# untitled.net
KiCad netlist of a schematic drawn in EAGLE
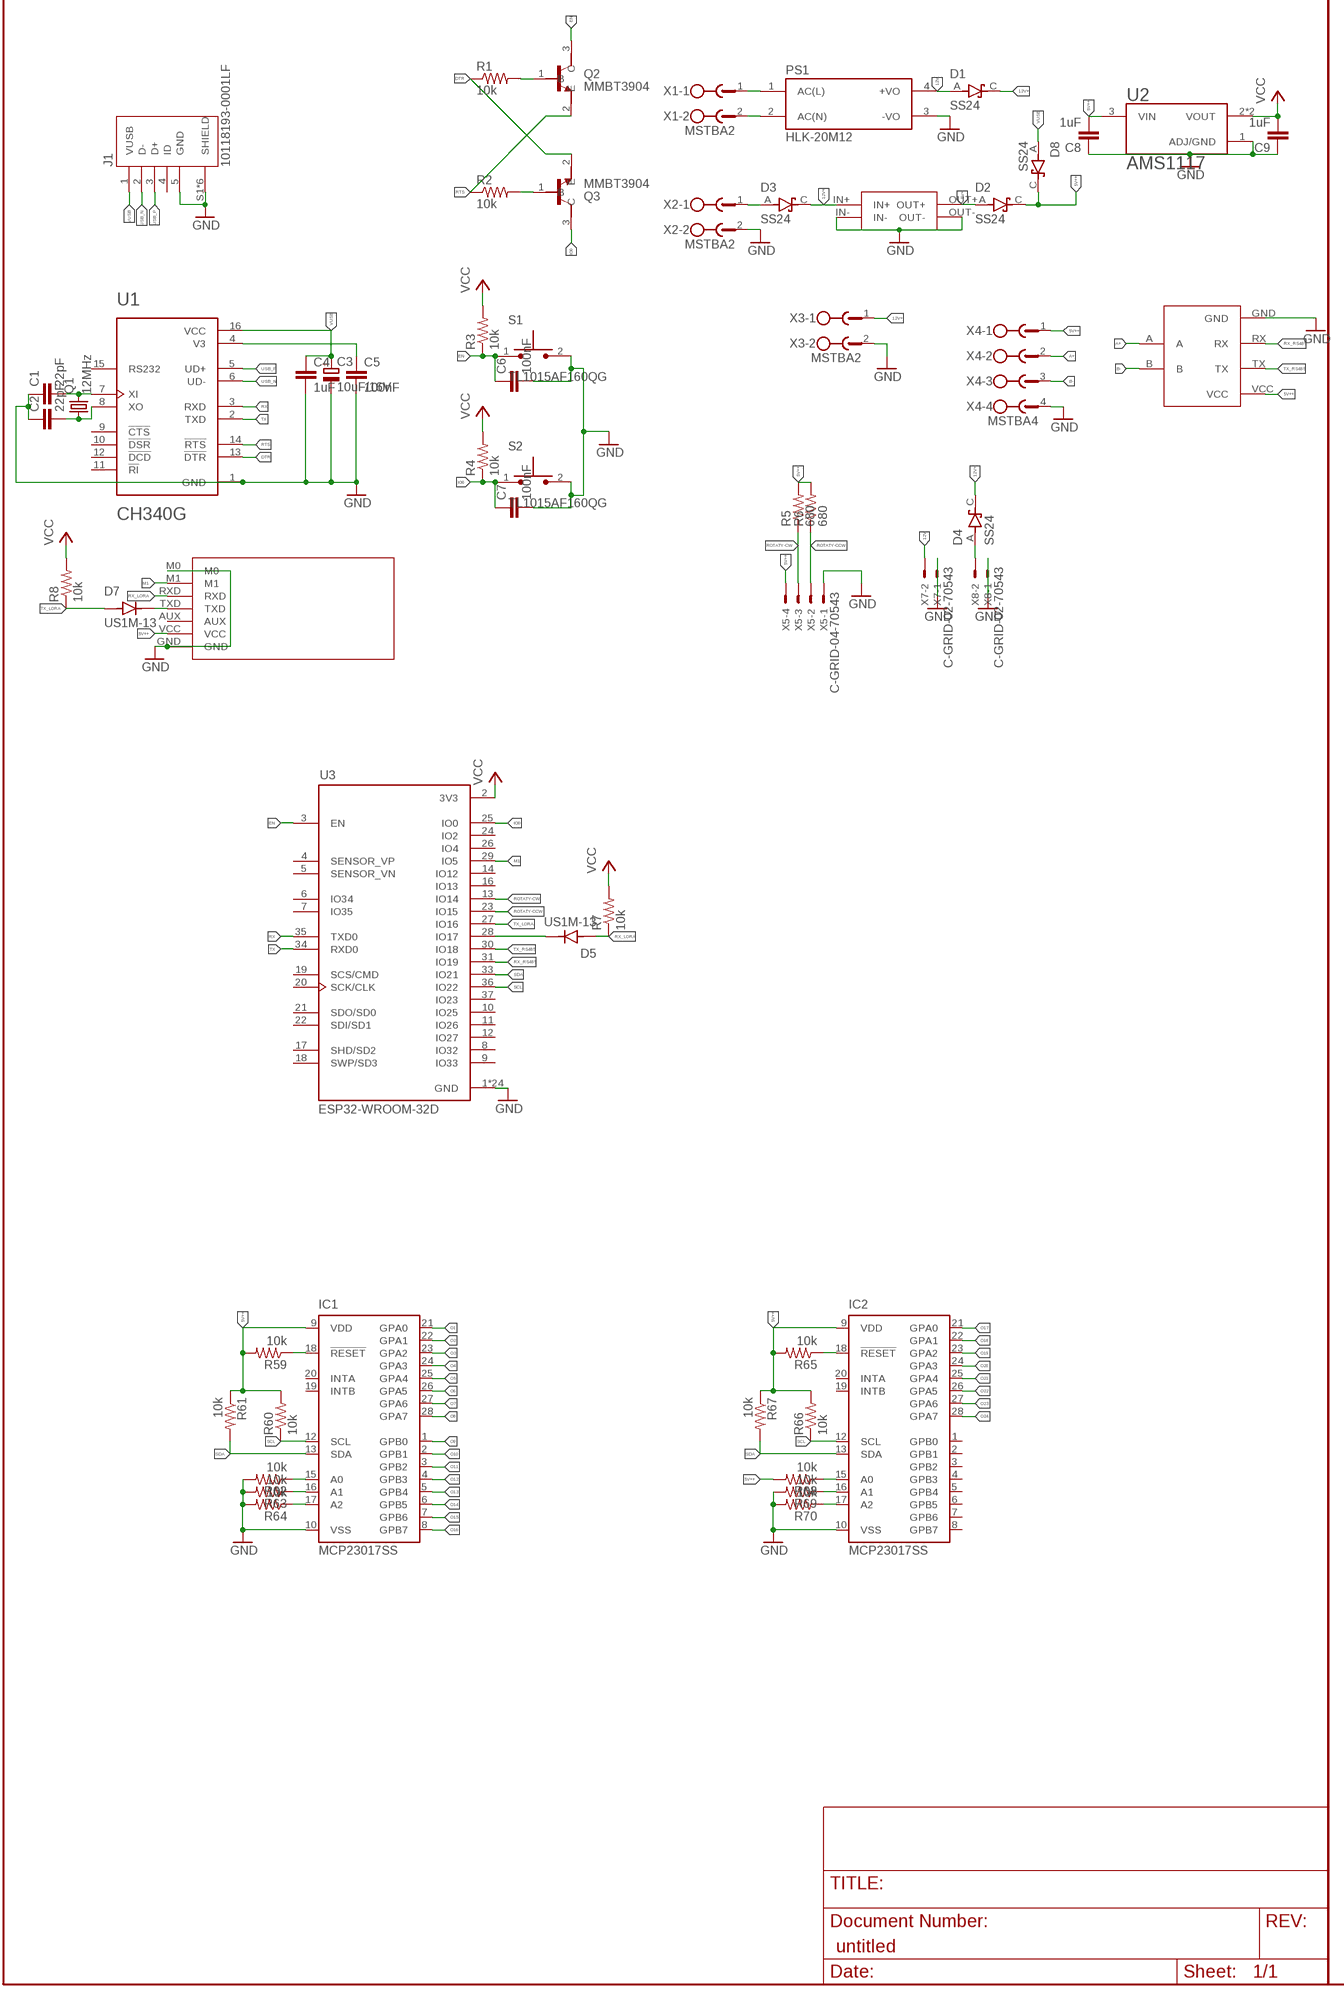
[diagram p0: schematic, sheet 1, part 1 of 2]
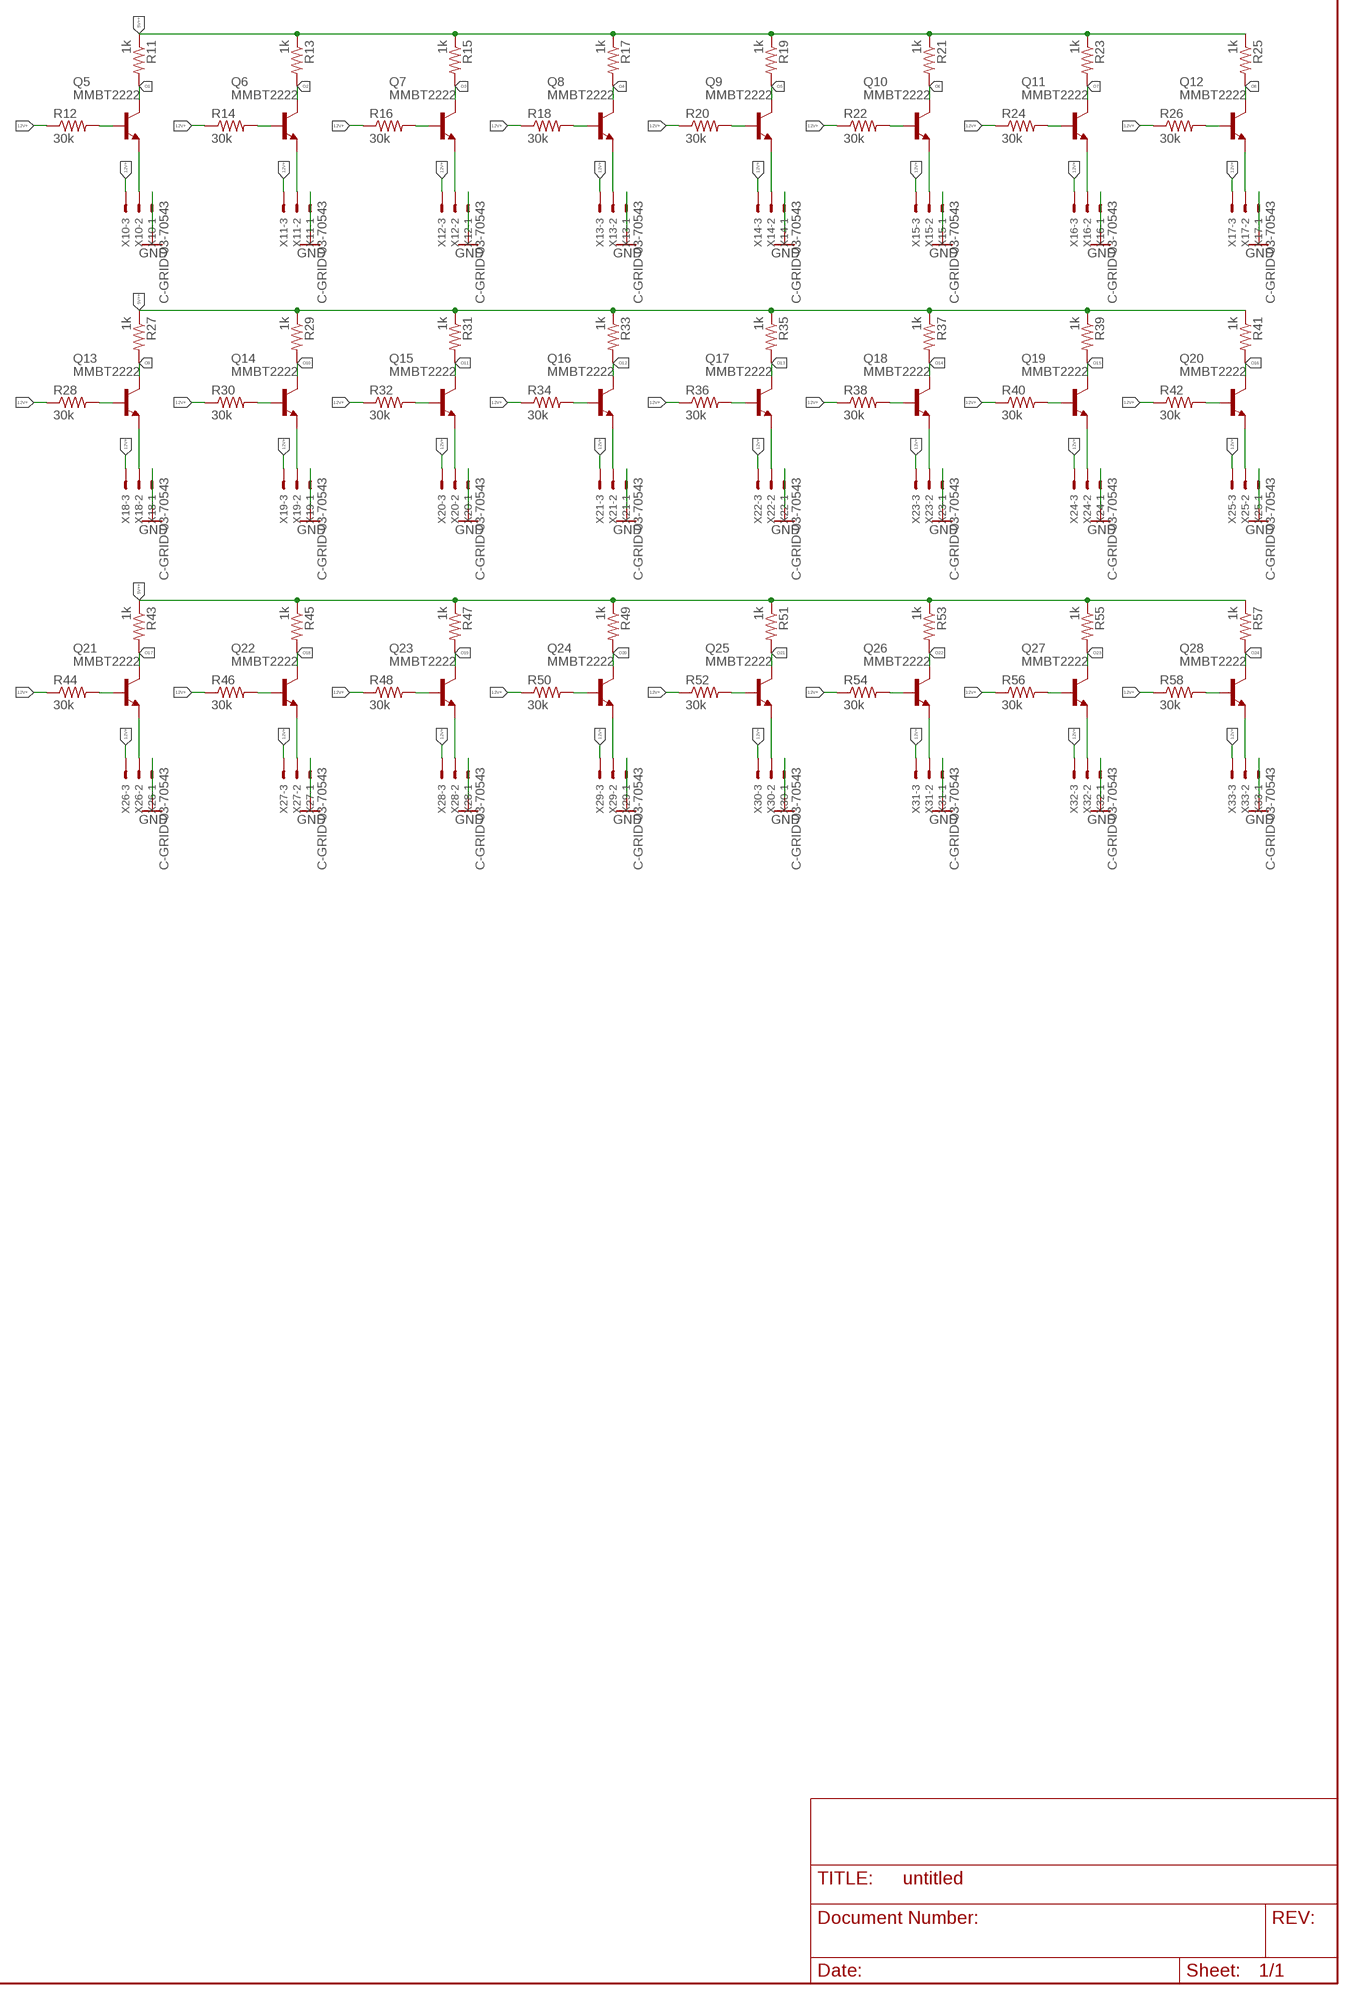
[diagram p1: schematic, sheet 1, part 2 of 2]

(export (version "E")
  (design (tool "Eeschema 10.0.6"))
  (components
    (comp (ref "C1")
      (value "22pF")
      (footprint "eagle-import:C0805K")
      (libsource (lib "eagle-import") (part "C-EUC0805K"))
    )
    (comp (ref "C2")
      (value "22pF")
      (footprint "eagle-import:C0805K")
      (libsource (lib "eagle-import") (part "C-EUC0805K"))
    )
    (comp (ref "C3")
      (value "10uF/16V")
      (footprint "eagle-import:153CLV-0505")
      (libsource (lib "eagle-import") (part "CPOL-EU153CLV-0505"))
    )
    (comp (ref "C4")
      (value "1uF")
      (footprint "eagle-import:C0805K")
      (libsource (lib "eagle-import") (part "C-EUC0805K"))
    )
    (comp (ref "C5")
      (value "100nF")
      (footprint "eagle-import:C0805K")
      (libsource (lib "eagle-import") (part "C-EUC0805K"))
    )
    (comp (ref "C6")
      (value "100nF")
      (footprint "eagle-import:C0805K")
      (libsource (lib "eagle-import") (part "C-EUC0805K"))
    )
    (comp (ref "C7")
      (value "100nF")
      (footprint "eagle-import:C0805K")
      (libsource (lib "eagle-import") (part "C-EUC0805K"))
    )
    (comp (ref "C8")
      (value "1uF")
      (footprint "eagle-import:C0805K")
      (libsource (lib "eagle-import") (part "C-EUC0805K"))
    )
    (comp (ref "C9")
      (value "1uF")
      (footprint "eagle-import:C0805K")
      (libsource (lib "eagle-import") (part "C-EUC0805K"))
    )
    (comp (ref "D1")
      (value "SS24")
      (footprint "eagle-import:DIOM5336X265N")
      (fields (field (name "MF") "ON Semiconductor"))
      (libsource (lib "eagle-import") (part "SS24"))
    )
    (comp (ref "D2")
      (value "SS24")
      (footprint "eagle-import:DIOM5336X265N")
      (fields (field (name "MF") "ON Semiconductor"))
      (libsource (lib "eagle-import") (part "SS24"))
    )
    (comp (ref "D3")
      (value "SS24")
      (footprint "eagle-import:DIOM5336X265N")
      (fields (field (name "MF") "ON Semiconductor"))
      (libsource (lib "eagle-import") (part "SS24"))
    )
    (comp (ref "D4")
      (value "SS24")
      (footprint "eagle-import:DIOM5336X265N")
      (fields (field (name "MF") "ON Semiconductor"))
      (libsource (lib "eagle-import") (part "SS24"))
    )
    (comp (ref "D5")
      (value "US1M-13")
      (footprint "eagle-import:DIOM5226X240N")
      (fields (field (name "MF") "Diodes Incorporated"))
      (libsource (lib "eagle-import") (part "US1M-13"))
    )
    (comp (ref "D7")
      (value "US1M-13")
      (footprint "eagle-import:DIOM5226X240N")
      (fields (field (name "MF") "Diodes Incorporated"))
      (libsource (lib "eagle-import") (part "US1M-13"))
    )
    (comp (ref "D8")
      (value "SS24")
      (footprint "eagle-import:DIOM5336X265N")
      (fields (field (name "MF") "ON Semiconductor"))
      (libsource (lib "eagle-import") (part "SS24"))
    )
    (comp (ref "EBYTEE220-900T22D1")
      (value "EBYTEE220-900T22D")
      (footprint "eagle-import:EBYTEE220-900T22D")
      (libsource (lib "eagle-import") (part "EBYTEE220-900T22D"))
    )
    (comp (ref "IC1")
      (value "MCP23017SS")
      (footprint "eagle-import:SSOP28")
      (libsource (lib "eagle-import") (part "MCP23017SS"))
    )
    (comp (ref "IC2")
      (value "MCP23017SS")
      (footprint "eagle-import:SSOP28")
      (libsource (lib "eagle-import") (part "MCP23017SS"))
    )
    (comp (ref "J1")
      (value "10118193-0001LF")
      (footprint "eagle-import:FCI_10118193-0001LF")
      (fields (field (name "MF") "FCI"))
      (libsource (lib "eagle-import") (part "10118193-0001LF"))
    )
    (comp (ref "MINI1")
      (value "MINI560")
      (footprint "eagle-import:MINI560")
      (libsource (lib "eagle-import") (part "MINI560"))
    )
    (comp (ref "PS1")
      (value "HLK-20M12")
      (footprint "eagle-import:CONV_HLK-20M12")
      (fields (field (name "MF") "Hi-link"))
      (libsource (lib "eagle-import") (part "HLK-20M12"))
    )
    (comp (ref "Q1")
      (value "12MHz")
      (footprint "eagle-import:SM49")
      (libsource (lib "eagle-import") (part "CRYSTALSM49"))
    )
    (comp (ref "Q2")
      (value "MMBT3904")
      (footprint "eagle-import:SOT95P240X120-3N")
      (fields (field (name "MF") "ON Semiconductor"))
      (libsource (lib "eagle-import") (part "MMBT3904"))
    )
    (comp (ref "Q3")
      (value "MMBT3904")
      (footprint "eagle-import:SOT95P240X120-3N")
      (fields (field (name "MF") "ON Semiconductor"))
      (libsource (lib "eagle-import") (part "MMBT3904"))
    )
    (comp (ref "Q5")
      (value "MMBT2222")
      (footprint "eagle-import:SOT23-BEC")
      (fields (field (name "MF") "ON Semiconductor"))
      (libsource (lib "eagle-import") (part "MMBT2222"))
    )
    (comp (ref "Q6")
      (value "MMBT2222")
      (footprint "eagle-import:SOT23-BEC")
      (fields (field (name "MF") "ON Semiconductor"))
      (libsource (lib "eagle-import") (part "MMBT2222"))
    )
    (comp (ref "Q7")
      (value "MMBT2222")
      (footprint "eagle-import:SOT23-BEC")
      (fields (field (name "MF") "ON Semiconductor"))
      (libsource (lib "eagle-import") (part "MMBT2222"))
    )
    (comp (ref "Q8")
      (value "MMBT2222")
      (footprint "eagle-import:SOT23-BEC")
      (fields (field (name "MF") "ON Semiconductor"))
      (libsource (lib "eagle-import") (part "MMBT2222"))
    )
    (comp (ref "Q9")
      (value "MMBT2222")
      (footprint "eagle-import:SOT23-BEC")
      (fields (field (name "MF") "ON Semiconductor"))
      (libsource (lib "eagle-import") (part "MMBT2222"))
    )
    (comp (ref "Q10")
      (value "MMBT2222")
      (footprint "eagle-import:SOT23-BEC")
      (fields (field (name "MF") "ON Semiconductor"))
      (libsource (lib "eagle-import") (part "MMBT2222"))
    )
    (comp (ref "Q11")
      (value "MMBT2222")
      (footprint "eagle-import:SOT23-BEC")
      (fields (field (name "MF") "ON Semiconductor"))
      (libsource (lib "eagle-import") (part "MMBT2222"))
    )
    (comp (ref "Q12")
      (value "MMBT2222")
      (footprint "eagle-import:SOT23-BEC")
      (fields (field (name "MF") "ON Semiconductor"))
      (libsource (lib "eagle-import") (part "MMBT2222"))
    )
    (comp (ref "Q13")
      (value "MMBT2222")
      (footprint "eagle-import:SOT23-BEC")
      (fields (field (name "MF") "ON Semiconductor"))
      (libsource (lib "eagle-import") (part "MMBT2222"))
    )
    (comp (ref "Q14")
      (value "MMBT2222")
      (footprint "eagle-import:SOT23-BEC")
      (fields (field (name "MF") "ON Semiconductor"))
      (libsource (lib "eagle-import") (part "MMBT2222"))
    )
    (comp (ref "Q15")
      (value "MMBT2222")
      (footprint "eagle-import:SOT23-BEC")
      (fields (field (name "MF") "ON Semiconductor"))
      (libsource (lib "eagle-import") (part "MMBT2222"))
    )
    (comp (ref "Q16")
      (value "MMBT2222")
      (footprint "eagle-import:SOT23-BEC")
      (fields (field (name "MF") "ON Semiconductor"))
      (libsource (lib "eagle-import") (part "MMBT2222"))
    )
    (comp (ref "Q17")
      (value "MMBT2222")
      (footprint "eagle-import:SOT23-BEC")
      (fields (field (name "MF") "ON Semiconductor"))
      (libsource (lib "eagle-import") (part "MMBT2222"))
    )
    (comp (ref "Q18")
      (value "MMBT2222")
      (footprint "eagle-import:SOT23-BEC")
      (fields (field (name "MF") "ON Semiconductor"))
      (libsource (lib "eagle-import") (part "MMBT2222"))
    )
    (comp (ref "Q19")
      (value "MMBT2222")
      (footprint "eagle-import:SOT23-BEC")
      (fields (field (name "MF") "ON Semiconductor"))
      (libsource (lib "eagle-import") (part "MMBT2222"))
    )
    (comp (ref "Q20")
      (value "MMBT2222")
      (footprint "eagle-import:SOT23-BEC")
      (fields (field (name "MF") "ON Semiconductor"))
      (libsource (lib "eagle-import") (part "MMBT2222"))
    )
    (comp (ref "Q21")
      (value "MMBT2222")
      (footprint "eagle-import:SOT23-BEC")
      (fields (field (name "MF") "ON Semiconductor"))
      (libsource (lib "eagle-import") (part "MMBT2222"))
    )
    (comp (ref "Q22")
      (value "MMBT2222")
      (footprint "eagle-import:SOT23-BEC")
      (fields (field (name "MF") "ON Semiconductor"))
      (libsource (lib "eagle-import") (part "MMBT2222"))
    )
    (comp (ref "Q23")
      (value "MMBT2222")
      (footprint "eagle-import:SOT23-BEC")
      (fields (field (name "MF") "ON Semiconductor"))
      (libsource (lib "eagle-import") (part "MMBT2222"))
    )
    (comp (ref "Q24")
      (value "MMBT2222")
      (footprint "eagle-import:SOT23-BEC")
      (fields (field (name "MF") "ON Semiconductor"))
      (libsource (lib "eagle-import") (part "MMBT2222"))
    )
    (comp (ref "Q25")
      (value "MMBT2222")
      (footprint "eagle-import:SOT23-BEC")
      (fields (field (name "MF") "ON Semiconductor"))
      (libsource (lib "eagle-import") (part "MMBT2222"))
    )
    (comp (ref "Q26")
      (value "MMBT2222")
      (footprint "eagle-import:SOT23-BEC")
      (fields (field (name "MF") "ON Semiconductor"))
      (libsource (lib "eagle-import") (part "MMBT2222"))
    )
    (comp (ref "Q27")
      (value "MMBT2222")
      (footprint "eagle-import:SOT23-BEC")
      (fields (field (name "MF") "ON Semiconductor"))
      (libsource (lib "eagle-import") (part "MMBT2222"))
    )
    (comp (ref "Q28")
      (value "MMBT2222")
      (footprint "eagle-import:SOT23-BEC")
      (fields (field (name "MF") "ON Semiconductor"))
      (libsource (lib "eagle-import") (part "MMBT2222"))
    )
    (comp (ref "R1")
      (value "10k")
      (footprint "eagle-import:M0805")
      (libsource (lib "eagle-import") (part "R-US_M0805"))
    )
    (comp (ref "R2")
      (value "10k")
      (footprint "eagle-import:M0805")
      (libsource (lib "eagle-import") (part "R-US_M0805"))
    )
    (comp (ref "R3")
      (value "10k")
      (footprint "eagle-import:M0805")
      (libsource (lib "eagle-import") (part "R-US_M0805"))
    )
    (comp (ref "R4")
      (value "10k")
      (footprint "eagle-import:M0805")
      (libsource (lib "eagle-import") (part "R-US_M0805"))
    )
    (comp (ref "R5")
      (value "680")
      (footprint "eagle-import:M0805")
      (libsource (lib "eagle-import") (part "R-US_M0805"))
    )
    (comp (ref "R6")
      (value "680")
      (footprint "eagle-import:M0805")
      (libsource (lib "eagle-import") (part "R-US_M0805"))
    )
    (comp (ref "R7")
      (value "10k")
      (footprint "eagle-import:M0805")
      (libsource (lib "eagle-import") (part "R-US_M0805"))
    )
    (comp (ref "R8")
      (value "10k")
      (footprint "eagle-import:M0805")
      (libsource (lib "eagle-import") (part "R-US_M0805"))
    )
    (comp (ref "R11")
      (value "1k")
      (footprint "eagle-import:M0805")
      (libsource (lib "eagle-import") (part "R-US_M0805"))
    )
    (comp (ref "R12")
      (value "30k")
      (footprint "eagle-import:M0805")
      (libsource (lib "eagle-import") (part "R-US_M0805"))
    )
    (comp (ref "R13")
      (value "1k")
      (footprint "eagle-import:M0805")
      (libsource (lib "eagle-import") (part "R-US_M0805"))
    )
    (comp (ref "R14")
      (value "30k")
      (footprint "eagle-import:M0805")
      (libsource (lib "eagle-import") (part "R-US_M0805"))
    )
    (comp (ref "R15")
      (value "1k")
      (footprint "eagle-import:M0805")
      (libsource (lib "eagle-import") (part "R-US_M0805"))
    )
    (comp (ref "R16")
      (value "30k")
      (footprint "eagle-import:M0805")
      (libsource (lib "eagle-import") (part "R-US_M0805"))
    )
    (comp (ref "R17")
      (value "1k")
      (footprint "eagle-import:M0805")
      (libsource (lib "eagle-import") (part "R-US_M0805"))
    )
    (comp (ref "R18")
      (value "30k")
      (footprint "eagle-import:M0805")
      (libsource (lib "eagle-import") (part "R-US_M0805"))
    )
    (comp (ref "R19")
      (value "1k")
      (footprint "eagle-import:M0805")
      (libsource (lib "eagle-import") (part "R-US_M0805"))
    )
    (comp (ref "R20")
      (value "30k")
      (footprint "eagle-import:M0805")
      (libsource (lib "eagle-import") (part "R-US_M0805"))
    )
    (comp (ref "R21")
      (value "1k")
      (footprint "eagle-import:M0805")
      (libsource (lib "eagle-import") (part "R-US_M0805"))
    )
    (comp (ref "R22")
      (value "30k")
      (footprint "eagle-import:M0805")
      (libsource (lib "eagle-import") (part "R-US_M0805"))
    )
    (comp (ref "R23")
      (value "1k")
      (footprint "eagle-import:M0805")
      (libsource (lib "eagle-import") (part "R-US_M0805"))
    )
    (comp (ref "R24")
      (value "30k")
      (footprint "eagle-import:M0805")
      (libsource (lib "eagle-import") (part "R-US_M0805"))
    )
    (comp (ref "R25")
      (value "1k")
      (footprint "eagle-import:M0805")
      (libsource (lib "eagle-import") (part "R-US_M0805"))
    )
    (comp (ref "R26")
      (value "30k")
      (footprint "eagle-import:M0805")
      (libsource (lib "eagle-import") (part "R-US_M0805"))
    )
    (comp (ref "R27")
      (value "1k")
      (footprint "eagle-import:M0805")
      (libsource (lib "eagle-import") (part "R-US_M0805"))
    )
    (comp (ref "R28")
      (value "30k")
      (footprint "eagle-import:M0805")
      (libsource (lib "eagle-import") (part "R-US_M0805"))
    )
    (comp (ref "R29")
      (value "1k")
      (footprint "eagle-import:M0805")
      (libsource (lib "eagle-import") (part "R-US_M0805"))
    )
    (comp (ref "R30")
      (value "30k")
      (footprint "eagle-import:M0805")
      (libsource (lib "eagle-import") (part "R-US_M0805"))
    )
    (comp (ref "R31")
      (value "1k")
      (footprint "eagle-import:M0805")
      (libsource (lib "eagle-import") (part "R-US_M0805"))
    )
    (comp (ref "R32")
      (value "30k")
      (footprint "eagle-import:M0805")
      (libsource (lib "eagle-import") (part "R-US_M0805"))
    )
    (comp (ref "R33")
      (value "1k")
      (footprint "eagle-import:M0805")
      (libsource (lib "eagle-import") (part "R-US_M0805"))
    )
    (comp (ref "R34")
      (value "30k")
      (footprint "eagle-import:M0805")
      (libsource (lib "eagle-import") (part "R-US_M0805"))
    )
    (comp (ref "R35")
      (value "1k")
      (footprint "eagle-import:M0805")
      (libsource (lib "eagle-import") (part "R-US_M0805"))
    )
    (comp (ref "R36")
      (value "30k")
      (footprint "eagle-import:M0805")
      (libsource (lib "eagle-import") (part "R-US_M0805"))
    )
    (comp (ref "R37")
      (value "1k")
      (footprint "eagle-import:M0805")
      (libsource (lib "eagle-import") (part "R-US_M0805"))
    )
    (comp (ref "R38")
      (value "30k")
      (footprint "eagle-import:M0805")
      (libsource (lib "eagle-import") (part "R-US_M0805"))
    )
    (comp (ref "R39")
      (value "1k")
      (footprint "eagle-import:M0805")
      (libsource (lib "eagle-import") (part "R-US_M0805"))
    )
    (comp (ref "R40")
      (value "30k")
      (footprint "eagle-import:M0805")
      (libsource (lib "eagle-import") (part "R-US_M0805"))
    )
    (comp (ref "R41")
      (value "1k")
      (footprint "eagle-import:M0805")
      (libsource (lib "eagle-import") (part "R-US_M0805"))
    )
    (comp (ref "R42")
      (value "30k")
      (footprint "eagle-import:M0805")
      (libsource (lib "eagle-import") (part "R-US_M0805"))
    )
    (comp (ref "R43")
      (value "1k")
      (footprint "eagle-import:M0805")
      (libsource (lib "eagle-import") (part "R-US_M0805"))
    )
    (comp (ref "R44")
      (value "30k")
      (footprint "eagle-import:M0805")
      (libsource (lib "eagle-import") (part "R-US_M0805"))
    )
    (comp (ref "R45")
      (value "1k")
      (footprint "eagle-import:M0805")
      (libsource (lib "eagle-import") (part "R-US_M0805"))
    )
    (comp (ref "R46")
      (value "30k")
      (footprint "eagle-import:M0805")
      (libsource (lib "eagle-import") (part "R-US_M0805"))
    )
    (comp (ref "R47")
      (value "1k")
      (footprint "eagle-import:M0805")
      (libsource (lib "eagle-import") (part "R-US_M0805"))
    )
    (comp (ref "R48")
      (value "30k")
      (footprint "eagle-import:M0805")
      (libsource (lib "eagle-import") (part "R-US_M0805"))
    )
    (comp (ref "R49")
      (value "1k")
      (footprint "eagle-import:M0805")
      (libsource (lib "eagle-import") (part "R-US_M0805"))
    )
    (comp (ref "R50")
      (value "30k")
      (footprint "eagle-import:M0805")
      (libsource (lib "eagle-import") (part "R-US_M0805"))
    )
    (comp (ref "R51")
      (value "1k")
      (footprint "eagle-import:M0805")
      (libsource (lib "eagle-import") (part "R-US_M0805"))
    )
    (comp (ref "R52")
      (value "30k")
      (footprint "eagle-import:M0805")
      (libsource (lib "eagle-import") (part "R-US_M0805"))
    )
    (comp (ref "R53")
      (value "1k")
      (footprint "eagle-import:M0805")
      (libsource (lib "eagle-import") (part "R-US_M0805"))
    )
    (comp (ref "R54")
      (value "30k")
      (footprint "eagle-import:M0805")
      (libsource (lib "eagle-import") (part "R-US_M0805"))
    )
    (comp (ref "R55")
      (value "1k")
      (footprint "eagle-import:M0805")
      (libsource (lib "eagle-import") (part "R-US_M0805"))
    )
    (comp (ref "R56")
      (value "30k")
      (footprint "eagle-import:M0805")
      (libsource (lib "eagle-import") (part "R-US_M0805"))
    )
    (comp (ref "R57")
      (value "1k")
      (footprint "eagle-import:M0805")
      (libsource (lib "eagle-import") (part "R-US_M0805"))
    )
    (comp (ref "R58")
      (value "30k")
      (footprint "eagle-import:M0805")
      (libsource (lib "eagle-import") (part "R-US_M0805"))
    )
    (comp (ref "R59")
      (value "10k")
      (footprint "eagle-import:M0805")
      (libsource (lib "eagle-import") (part "R-US_M0805"))
    )
    (comp (ref "R60")
      (value "10k")
      (footprint "eagle-import:M0805")
      (libsource (lib "eagle-import") (part "R-US_M0805"))
    )
    (comp (ref "R61")
      (value "10k")
      (footprint "eagle-import:M0805")
      (libsource (lib "eagle-import") (part "R-US_M0805"))
    )
    (comp (ref "R62")
      (value "10k")
      (footprint "eagle-import:M0805")
      (libsource (lib "eagle-import") (part "R-US_M0805"))
    )
    (comp (ref "R63")
      (value "10k")
      (footprint "eagle-import:M0805")
      (libsource (lib "eagle-import") (part "R-US_M0805"))
    )
    (comp (ref "R64")
      (value "10k")
      (footprint "eagle-import:M0805")
      (libsource (lib "eagle-import") (part "R-US_M0805"))
    )
    (comp (ref "R65")
      (value "10k")
      (footprint "eagle-import:M0805")
      (libsource (lib "eagle-import") (part "R-US_M0805"))
    )
    (comp (ref "R66")
      (value "10k")
      (footprint "eagle-import:M0805")
      (libsource (lib "eagle-import") (part "R-US_M0805"))
    )
    (comp (ref "R67")
      (value "10k")
      (footprint "eagle-import:M0805")
      (libsource (lib "eagle-import") (part "R-US_M0805"))
    )
    (comp (ref "R68")
      (value "10k")
      (footprint "eagle-import:M0805")
      (libsource (lib "eagle-import") (part "R-US_M0805"))
    )
    (comp (ref "R69")
      (value "10k")
      (footprint "eagle-import:M0805")
      (libsource (lib "eagle-import") (part "R-US_M0805"))
    )
    (comp (ref "R70")
      (value "10k")
      (footprint "eagle-import:M0805")
      (libsource (lib "eagle-import") (part "R-US_M0805"))
    )
    (comp (ref "S1")
      (value "TL1015AF160QG")
      (footprint "eagle-import:SW_TL1015AF160QG")
      (fields (field (name "MF") "E-Switch"))
      (libsource (lib "eagle-import") (part "TL1015AF160QG"))
    )
    (comp (ref "S2")
      (value "TL1015AF160QG")
      (footprint "eagle-import:SW_TL1015AF160QG")
      (fields (field (name "MF") "E-Switch"))
      (libsource (lib "eagle-import") (part "TL1015AF160QG"))
    )
    (comp (ref "TTL-RS1")
      (value "TTL-RS485")
      (footprint "eagle-import:TTL-RS485")
      (libsource (lib "eagle-import") (part "TTL-RS485"))
    )
    (comp (ref "U1")
      (value "CH340G")
      (footprint "eagle-import:SOIC127P600X180-16N")
      (fields (field (name "MF") "WCH") (field (name "MP") "Ch340G"))
      (libsource (lib "eagle-import") (part "CH340G"))
    )
    (comp (ref "U2")
      (value "AMS1117")
      (footprint "eagle-import:SOT229P700X180-4N")
      (fields (field (name "MF") "Advanced Monolithic Systems"))
      (libsource (lib "eagle-import") (part "AMS1117"))
    )
    (comp (ref "U3")
      (value "ESP32-WROOM-32D")
      (footprint "eagle-import:MODULE_ESP32-WROOM-32D")
      (fields (field (name "MF") "Espressif Systems"))
      (libsource (lib "eagle-import") (part "ESP32-WROOM-32D"))
    )
    (comp (ref "X1")
      (value "MSTBA2")
      (footprint "eagle-import:MSTBA2")
      (fields (field (name "MF") "FARNELL") (field (name "MPN") "1757242"))
      (libsource (lib "eagle-import") (part "MSTBA2"))
    )
    (comp (ref "X2")
      (value "MSTBA2")
      (footprint "eagle-import:MSTBA2")
      (fields (field (name "MF") "FARNELL") (field (name "MPN") "1757242"))
      (libsource (lib "eagle-import") (part "MSTBA2"))
    )
    (comp (ref "X3")
      (value "MSTBA2")
      (footprint "eagle-import:MSTBA2")
      (fields (field (name "MF") "FARNELL") (field (name "MPN") "1757242"))
      (libsource (lib "eagle-import") (part "MSTBA2"))
    )
    (comp (ref "X4")
      (value "MSTBA4")
      (footprint "eagle-import:MSTBA4")
      (fields (field (name "MF") "FARNELL") (field (name "MPN") "1757268"))
      (libsource (lib "eagle-import") (part "MSTBA4"))
    )
    (comp (ref "X5")
      (value "C-GRID-04-70543")
      (footprint "eagle-import:70543-04")
      (fields (field (name "MF") "MOLEX"))
      (libsource (lib "eagle-import") (part "C-GRID-04-70543"))
    )
    (comp (ref "X7")
      (value "C-GRID-02-70543")
      (footprint "eagle-import:70543-02")
      (fields (field (name "MF") "MOLEX"))
      (libsource (lib "eagle-import") (part "C-GRID-02-70543"))
    )
    (comp (ref "X8")
      (value "C-GRID-02-70543")
      (footprint "eagle-import:70543-02")
      (fields (field (name "MF") "MOLEX"))
      (libsource (lib "eagle-import") (part "C-GRID-02-70543"))
    )
    (comp (ref "X10")
      (value "C-GRID-03-70543")
      (footprint "eagle-import:70543-03")
      (fields (field (name "MF") "MOLEX"))
      (libsource (lib "eagle-import") (part "C-GRID-03-70543"))
    )
    (comp (ref "X11")
      (value "C-GRID-03-70543")
      (footprint "eagle-import:70543-03")
      (fields (field (name "MF") "MOLEX"))
      (libsource (lib "eagle-import") (part "C-GRID-03-70543"))
    )
    (comp (ref "X12")
      (value "C-GRID-03-70543")
      (footprint "eagle-import:70543-03")
      (fields (field (name "MF") "MOLEX"))
      (libsource (lib "eagle-import") (part "C-GRID-03-70543"))
    )
    (comp (ref "X13")
      (value "C-GRID-03-70543")
      (footprint "eagle-import:70543-03")
      (fields (field (name "MF") "MOLEX"))
      (libsource (lib "eagle-import") (part "C-GRID-03-70543"))
    )
    (comp (ref "X14")
      (value "C-GRID-03-70543")
      (footprint "eagle-import:70543-03")
      (fields (field (name "MF") "MOLEX"))
      (libsource (lib "eagle-import") (part "C-GRID-03-70543"))
    )
    (comp (ref "X15")
      (value "C-GRID-03-70543")
      (footprint "eagle-import:70543-03")
      (fields (field (name "MF") "MOLEX"))
      (libsource (lib "eagle-import") (part "C-GRID-03-70543"))
    )
    (comp (ref "X16")
      (value "C-GRID-03-70543")
      (footprint "eagle-import:70543-03")
      (fields (field (name "MF") "MOLEX"))
      (libsource (lib "eagle-import") (part "C-GRID-03-70543"))
    )
    (comp (ref "X17")
      (value "C-GRID-03-70543")
      (footprint "eagle-import:70543-03")
      (fields (field (name "MF") "MOLEX"))
      (libsource (lib "eagle-import") (part "C-GRID-03-70543"))
    )
    (comp (ref "X18")
      (value "C-GRID-03-70543")
      (footprint "eagle-import:70543-03")
      (fields (field (name "MF") "MOLEX"))
      (libsource (lib "eagle-import") (part "C-GRID-03-70543"))
    )
    (comp (ref "X19")
      (value "C-GRID-03-70543")
      (footprint "eagle-import:70543-03")
      (fields (field (name "MF") "MOLEX"))
      (libsource (lib "eagle-import") (part "C-GRID-03-70543"))
    )
    (comp (ref "X20")
      (value "C-GRID-03-70543")
      (footprint "eagle-import:70543-03")
      (fields (field (name "MF") "MOLEX"))
      (libsource (lib "eagle-import") (part "C-GRID-03-70543"))
    )
    (comp (ref "X21")
      (value "C-GRID-03-70543")
      (footprint "eagle-import:70543-03")
      (fields (field (name "MF") "MOLEX"))
      (libsource (lib "eagle-import") (part "C-GRID-03-70543"))
    )
    (comp (ref "X22")
      (value "C-GRID-03-70543")
      (footprint "eagle-import:70543-03")
      (fields (field (name "MF") "MOLEX"))
      (libsource (lib "eagle-import") (part "C-GRID-03-70543"))
    )
    (comp (ref "X23")
      (value "C-GRID-03-70543")
      (footprint "eagle-import:70543-03")
      (fields (field (name "MF") "MOLEX"))
      (libsource (lib "eagle-import") (part "C-GRID-03-70543"))
    )
    (comp (ref "X24")
      (value "C-GRID-03-70543")
      (footprint "eagle-import:70543-03")
      (fields (field (name "MF") "MOLEX"))
      (libsource (lib "eagle-import") (part "C-GRID-03-70543"))
    )
    (comp (ref "X25")
      (value "C-GRID-03-70543")
      (footprint "eagle-import:70543-03")
      (fields (field (name "MF") "MOLEX"))
      (libsource (lib "eagle-import") (part "C-GRID-03-70543"))
    )
    (comp (ref "X26")
      (value "C-GRID-03-70543")
      (footprint "eagle-import:70543-03")
      (fields (field (name "MF") "MOLEX"))
      (libsource (lib "eagle-import") (part "C-GRID-03-70543"))
    )
    (comp (ref "X27")
      (value "C-GRID-03-70543")
      (footprint "eagle-import:70543-03")
      (fields (field (name "MF") "MOLEX"))
      (libsource (lib "eagle-import") (part "C-GRID-03-70543"))
    )
    (comp (ref "X28")
      (value "C-GRID-03-70543")
      (footprint "eagle-import:70543-03")
      (fields (field (name "MF") "MOLEX"))
      (libsource (lib "eagle-import") (part "C-GRID-03-70543"))
    )
    (comp (ref "X29")
      (value "C-GRID-03-70543")
      (footprint "eagle-import:70543-03")
      (fields (field (name "MF") "MOLEX"))
      (libsource (lib "eagle-import") (part "C-GRID-03-70543"))
    )
    (comp (ref "X30")
      (value "C-GRID-03-70543")
      (footprint "eagle-import:70543-03")
      (fields (field (name "MF") "MOLEX"))
      (libsource (lib "eagle-import") (part "C-GRID-03-70543"))
    )
    (comp (ref "X31")
      (value "C-GRID-03-70543")
      (footprint "eagle-import:70543-03")
      (fields (field (name "MF") "MOLEX"))
      (libsource (lib "eagle-import") (part "C-GRID-03-70543"))
    )
    (comp (ref "X32")
      (value "C-GRID-03-70543")
      (footprint "eagle-import:70543-03")
      (fields (field (name "MF") "MOLEX"))
      (libsource (lib "eagle-import") (part "C-GRID-03-70543"))
    )
    (comp (ref "X33")
      (value "C-GRID-03-70543")
      (footprint "eagle-import:70543-03")
      (fields (field (name "MF") "MOLEX"))
      (libsource (lib "eagle-import") (part "C-GRID-03-70543"))
    )
  )
  (nets
    (net (code "1") (name "5V+") (class "Default")
      (node (ref "D2") (pin "A") (pinfunction "A_A") (pintype "passive"))
      (node (ref "MINI1") (pin "OUT+") (pinfunction "OUT+_OUT+") (pintype "bidirectional"))
    )
    (net (code "2") (name "5V++") (class "Default")
      (node (ref "C8") (pin "2") (pinfunction "2_2") (pintype "passive"))
      (node (ref "D2") (pin "C") (pinfunction "K_C") (pintype "passive"))
      (node (ref "D8") (pin "C") (pinfunction "K_C") (pintype "passive"))
      (node (ref "EBYTEE220-900T22D1") (pin "VCC") (pinfunction "VCC_VCC") (pintype "bidirectional"))
      (node (ref "IC1") (pin "9") (pinfunction "VDD_9") (pintype "power_in"))
      (node (ref "IC2") (pin "9") (pinfunction "VDD_9") (pintype "power_in"))
      (node (ref "R11") (pin "1") (pinfunction "1_1") (pintype "passive"))
      (node (ref "R13") (pin "1") (pinfunction "1_1") (pintype "passive"))
      (node (ref "R15") (pin "1") (pinfunction "1_1") (pintype "passive"))
      (node (ref "R17") (pin "1") (pinfunction "1_1") (pintype "passive"))
      (node (ref "R19") (pin "1") (pinfunction "1_1") (pintype "passive"))
      (node (ref "R21") (pin "1") (pinfunction "1_1") (pintype "passive"))
      (node (ref "R23") (pin "1") (pinfunction "1_1") (pintype "passive"))
      (node (ref "R25") (pin "1") (pinfunction "1_1") (pintype "passive"))
      (node (ref "R27") (pin "1") (pinfunction "1_1") (pintype "passive"))
      (node (ref "R29") (pin "1") (pinfunction "1_1") (pintype "passive"))
      (node (ref "R31") (pin "1") (pinfunction "1_1") (pintype "passive"))
      (node (ref "R33") (pin "1") (pinfunction "1_1") (pintype "passive"))
      (node (ref "R35") (pin "1") (pinfunction "1_1") (pintype "passive"))
      (node (ref "R37") (pin "1") (pinfunction "1_1") (pintype "passive"))
      (node (ref "R39") (pin "1") (pinfunction "1_1") (pintype "passive"))
      (node (ref "R41") (pin "1") (pinfunction "1_1") (pintype "passive"))
      (node (ref "R43") (pin "1") (pinfunction "1_1") (pintype "passive"))
      (node (ref "R45") (pin "1") (pinfunction "1_1") (pintype "passive"))
      (node (ref "R47") (pin "1") (pinfunction "1_1") (pintype "passive"))
      (node (ref "R49") (pin "1") (pinfunction "1_1") (pintype "passive"))
      (node (ref "R5") (pin "2") (pinfunction "2_2") (pintype "passive"))
      (node (ref "R51") (pin "1") (pinfunction "1_1") (pintype "passive"))
      (node (ref "R53") (pin "1") (pinfunction "1_1") (pintype "passive"))
      (node (ref "R55") (pin "1") (pinfunction "1_1") (pintype "passive"))
      (node (ref "R57") (pin "1") (pinfunction "1_1") (pintype "passive"))
      (node (ref "R59") (pin "2") (pinfunction "2_2") (pintype "passive"))
      (node (ref "R6") (pin "2") (pinfunction "2_2") (pintype "passive"))
      (node (ref "R60") (pin "2") (pinfunction "2_2") (pintype "passive"))
      (node (ref "R61") (pin "1") (pinfunction "1_1") (pintype "passive"))
      (node (ref "R65") (pin "2") (pinfunction "2_2") (pintype "passive"))
      (node (ref "R66") (pin "2") (pinfunction "2_2") (pintype "passive"))
      (node (ref "R67") (pin "1") (pinfunction "1_1") (pintype "passive"))
      (node (ref "R68") (pin "2") (pinfunction "2_2") (pintype "passive"))
      (node (ref "TTL-RS1") (pin "VCC") (pinfunction "VCC_VCC") (pintype "bidirectional"))
      (node (ref "U2") (pin "3") (pinfunction "VIN_3") (pintype "input"))
      (node (ref "X4") (pin "1") (pinfunction "1_1") (pintype "passive"))
      (node (ref "X5") (pin "4") (pinfunction "S_4") (pintype "passive"))
    )
    (net (code "3") (name "12V") (class "Default")
      (node (ref "D1") (pin "A") (pinfunction "A_A") (pintype "passive"))
      (node (ref "PS1") (pin "4") (pinfunction "+VO_4") (pintype "output"))
      (node (ref "X7") (pin "2") (pinfunction "S_2") (pintype "passive"))
    )
    (net (code "4") (name "12V+") (class "Default")
      (node (ref "D1") (pin "C") (pinfunction "K_C") (pintype "passive"))
      (node (ref "D3") (pin "C") (pinfunction "K_C") (pintype "passive"))
      (node (ref "D4") (pin "C") (pinfunction "K_C") (pintype "passive"))
      (node (ref "MINI1") (pin "IN+") (pinfunction "IN+_IN+") (pintype "bidirectional"))
      (node (ref "R12") (pin "1") (pinfunction "1_1") (pintype "passive"))
      (node (ref "R14") (pin "1") (pinfunction "1_1") (pintype "passive"))
      (node (ref "R16") (pin "1") (pinfunction "1_1") (pintype "passive"))
      (node (ref "R18") (pin "1") (pinfunction "1_1") (pintype "passive"))
      (node (ref "R20") (pin "1") (pinfunction "1_1") (pintype "passive"))
      (node (ref "R22") (pin "1") (pinfunction "1_1") (pintype "passive"))
      (node (ref "R24") (pin "1") (pinfunction "1_1") (pintype "passive"))
      (node (ref "R26") (pin "1") (pinfunction "1_1") (pintype "passive"))
      (node (ref "R28") (pin "1") (pinfunction "1_1") (pintype "passive"))
      (node (ref "R30") (pin "1") (pinfunction "1_1") (pintype "passive"))
      (node (ref "R32") (pin "1") (pinfunction "1_1") (pintype "passive"))
      (node (ref "R34") (pin "1") (pinfunction "1_1") (pintype "passive"))
      (node (ref "R36") (pin "1") (pinfunction "1_1") (pintype "passive"))
      (node (ref "R38") (pin "1") (pinfunction "1_1") (pintype "passive"))
      (node (ref "R40") (pin "1") (pinfunction "1_1") (pintype "passive"))
      (node (ref "R42") (pin "1") (pinfunction "1_1") (pintype "passive"))
      (node (ref "R44") (pin "1") (pinfunction "1_1") (pintype "passive"))
      (node (ref "R46") (pin "1") (pinfunction "1_1") (pintype "passive"))
      (node (ref "R48") (pin "1") (pinfunction "1_1") (pintype "passive"))
      (node (ref "R50") (pin "1") (pinfunction "1_1") (pintype "passive"))
      (node (ref "R52") (pin "1") (pinfunction "1_1") (pintype "passive"))
      (node (ref "R54") (pin "1") (pinfunction "1_1") (pintype "passive"))
      (node (ref "R56") (pin "1") (pinfunction "1_1") (pintype "passive"))
      (node (ref "R58") (pin "1") (pinfunction "1_1") (pintype "passive"))
      (node (ref "X10") (pin "3") (pinfunction "S_3") (pintype "passive"))
      (node (ref "X11") (pin "3") (pinfunction "S_3") (pintype "passive"))
      (node (ref "X12") (pin "3") (pinfunction "S_3") (pintype "passive"))
      (node (ref "X13") (pin "3") (pinfunction "S_3") (pintype "passive"))
      (node (ref "X14") (pin "3") (pinfunction "S_3") (pintype "passive"))
      (node (ref "X15") (pin "3") (pinfunction "S_3") (pintype "passive"))
      (node (ref "X16") (pin "3") (pinfunction "S_3") (pintype "passive"))
      (node (ref "X17") (pin "3") (pinfunction "S_3") (pintype "passive"))
      (node (ref "X18") (pin "3") (pinfunction "S_3") (pintype "passive"))
      (node (ref "X19") (pin "3") (pinfunction "S_3") (pintype "passive"))
      (node (ref "X20") (pin "3") (pinfunction "S_3") (pintype "passive"))
      (node (ref "X21") (pin "3") (pinfunction "S_3") (pintype "passive"))
      (node (ref "X22") (pin "3") (pinfunction "S_3") (pintype "passive"))
      (node (ref "X23") (pin "3") (pinfunction "S_3") (pintype "passive"))
      (node (ref "X24") (pin "3") (pinfunction "S_3") (pintype "passive"))
      (node (ref "X25") (pin "3") (pinfunction "S_3") (pintype "passive"))
      (node (ref "X26") (pin "3") (pinfunction "S_3") (pintype "passive"))
      (node (ref "X27") (pin "3") (pinfunction "S_3") (pintype "passive"))
      (node (ref "X28") (pin "3") (pinfunction "S_3") (pintype "passive"))
      (node (ref "X29") (pin "3") (pinfunction "S_3") (pintype "passive"))
      (node (ref "X3") (pin "1") (pinfunction "1_1") (pintype "passive"))
      (node (ref "X30") (pin "3") (pinfunction "S_3") (pintype "passive"))
      (node (ref "X31") (pin "3") (pinfunction "S_3") (pintype "passive"))
      (node (ref "X32") (pin "3") (pinfunction "S_3") (pintype "passive"))
      (node (ref "X33") (pin "3") (pinfunction "S_3") (pintype "passive"))
    )
    (net (code "5") (name "A+") (class "Default")
      (node (ref "TTL-RS1") (pin "A") (pinfunction "A_A") (pintype "bidirectional"))
      (node (ref "X4") (pin "2") (pinfunction "1_2") (pintype "passive"))
    )
    (net (code "6") (name "B-") (class "Default")
      (node (ref "TTL-RS1") (pin "B") (pinfunction "B_B") (pintype "bidirectional"))
      (node (ref "X4") (pin "3") (pinfunction "1_3") (pintype "passive"))
    )
    (net (code "7") (name "DTR") (class "Default")
      (node (ref "Q3") (pin "2") (pinfunction "E_2") (pintype "passive"))
      (node (ref "R1") (pin "1") (pinfunction "1_1") (pintype "passive"))
      (node (ref "U1") (pin "13") (pinfunction "~{DTR}_13") (pintype "output"))
    )
    (net (code "8") (name "EN") (class "Default")
      (node (ref "C6") (pin "1") (pinfunction "1_1") (pintype "passive"))
      (node (ref "Q2") (pin "3") (pinfunction "C_3") (pintype "passive"))
      (node (ref "R3") (pin "1") (pinfunction "1_1") (pintype "passive"))
      (node (ref "S1") (pin "1") (pinfunction "1_1") (pintype "passive"))
      (node (ref "U3") (pin "3") (pinfunction "EN_3") (pintype "input"))
    )
    (net (code "9") (name "GND") (class "Default")
      (node (ref "C1") (pin "1") (pinfunction "1_1") (pintype "passive"))
      (node (ref "C2") (pin "1") (pinfunction "1_1") (pintype "passive"))
      (node (ref "C3") (pin "-") (pinfunction "-_-") (pintype "passive"))
      (node (ref "C4") (pin "2") (pinfunction "2_2") (pintype "passive"))
      (node (ref "C5") (pin "2") (pinfunction "2_2") (pintype "passive"))
      (node (ref "C6") (pin "2") (pinfunction "2_2") (pintype "passive"))
      (node (ref "C7") (pin "2") (pinfunction "2_2") (pintype "passive"))
      (node (ref "C8") (pin "1") (pinfunction "1_1") (pintype "passive"))
      (node (ref "C9") (pin "1") (pinfunction "1_1") (pintype "passive"))
      (node (ref "EBYTEE220-900T22D1") (pin "GND") (pinfunction "GND_GND") (pintype "bidirectional"))
      (node (ref "EBYTEE220-900T22D1") (pin "M0") (pinfunction "M0_M0") (pintype "bidirectional"))
      (node (ref "IC1") (pin "10") (pinfunction "VSS_10") (pintype "power_in"))
      (node (ref "IC2") (pin "10") (pinfunction "VSS_10") (pintype "power_in"))
      (node (ref "J1") (pin "5") (pinfunction "GND_5") (pintype "passive"))
      (node (ref "J1") (pin "S1") (pinfunction "SHIELD_S1") (pintype "passive"))
      (node (ref "J1") (pin "S2") (pinfunction "SHIELD_S2") (pintype "passive"))
      (node (ref "J1") (pin "S3") (pinfunction "SHIELD_S3") (pintype "passive"))
      (node (ref "J1") (pin "S4") (pinfunction "SHIELD_S4") (pintype "passive"))
      (node (ref "J1") (pin "S5") (pinfunction "SHIELD_S5") (pintype "passive"))
      (node (ref "J1") (pin "S6") (pinfunction "SHIELD_S6") (pintype "passive"))
      (node (ref "MINI1") (pin "IN-") (pinfunction "IN-_IN-") (pintype "bidirectional"))
      (node (ref "MINI1") (pin "OUT-") (pinfunction "OUT-_OUT-") (pintype "bidirectional"))
      (node (ref "PS1") (pin "3") (pinfunction "-VO_3") (pintype "output"))
      (node (ref "R62") (pin "2") (pinfunction "2_2") (pintype "passive"))
      (node (ref "R63") (pin "2") (pinfunction "2_2") (pintype "passive"))
      (node (ref "R64") (pin "2") (pinfunction "2_2") (pintype "passive"))
      (node (ref "R69") (pin "2") (pinfunction "2_2") (pintype "passive"))
      (node (ref "R70") (pin "2") (pinfunction "2_2") (pintype "passive"))
      (node (ref "S1") (pin "2") (pinfunction "2_2") (pintype "passive"))
      (node (ref "S2") (pin "2") (pinfunction "2_2") (pintype "passive"))
      (node (ref "TTL-RS1") (pin "GND") (pinfunction "GND_GND") (pintype "bidirectional"))
      (node (ref "U1") (pin "1") (pinfunction "GND_1") (pintype "power_in"))
      (node (ref "U2") (pin "1") (pinfunction "ADJ/GND_1") (pintype "power_in"))
      (node (ref "U3") (pin "1") (pinfunction "GND_1") (pintype "power_in"))
      (node (ref "U3") (pin "15") (pinfunction "GND_15") (pintype "power_in"))
      (node (ref "U3") (pin "38") (pinfunction "GND_38") (pintype "power_in"))
      (node (ref "U3") (pin "39_1") (pinfunction "GND_39_1") (pintype "power_in"))
      (node (ref "U3") (pin "39_10") (pinfunction "GND_39_10") (pintype "power_in"))
      (node (ref "U3") (pin "39_11") (pinfunction "GND_39_11") (pintype "power_in"))
      (node (ref "U3") (pin "39_12") (pinfunction "GND_39_12") (pintype "power_in"))
      (node (ref "U3") (pin "39_13") (pinfunction "GND_39_13") (pintype "power_in"))
      (node (ref "U3") (pin "39_14") (pinfunction "GND_39_14") (pintype "power_in"))
      (node (ref "U3") (pin "39_15") (pinfunction "GND_39_15") (pintype "power_in"))
      (node (ref "U3") (pin "39_16") (pinfunction "GND_39_16") (pintype "power_in"))
      (node (ref "U3") (pin "39_17") (pinfunction "GND_39_17") (pintype "power_in"))
      (node (ref "U3") (pin "39_18") (pinfunction "GND_39_18") (pintype "power_in"))
      (node (ref "U3") (pin "39_19") (pinfunction "GND_39_19") (pintype "power_in"))
      (node (ref "U3") (pin "39_2") (pinfunction "GND_39_2") (pintype "power_in"))
      (node (ref "U3") (pin "39_20") (pinfunction "GND_39_20") (pintype "power_in"))
      (node (ref "U3") (pin "39_21") (pinfunction "GND_39_21") (pintype "power_in"))
      (node (ref "U3") (pin "39_3") (pinfunction "GND_39_3") (pintype "power_in"))
      (node (ref "U3") (pin "39_4") (pinfunction "GND_39_4") (pintype "power_in"))
      (node (ref "U3") (pin "39_5") (pinfunction "GND_39_5") (pintype "power_in"))
      (node (ref "U3") (pin "39_6") (pinfunction "GND_39_6") (pintype "power_in"))
      (node (ref "U3") (pin "39_7") (pinfunction "GND_39_7") (pintype "power_in"))
      (node (ref "U3") (pin "39_8") (pinfunction "GND_39_8") (pintype "power_in"))
      (node (ref "U3") (pin "39_9") (pinfunction "GND_39_9") (pintype "power_in"))
      (node (ref "X10") (pin "1") (pinfunction "S_1") (pintype "passive"))
      (node (ref "X11") (pin "1") (pinfunction "S_1") (pintype "passive"))
      (node (ref "X12") (pin "1") (pinfunction "S_1") (pintype "passive"))
      (node (ref "X13") (pin "1") (pinfunction "S_1") (pintype "passive"))
      (node (ref "X14") (pin "1") (pinfunction "S_1") (pintype "passive"))
      (node (ref "X15") (pin "1") (pinfunction "S_1") (pintype "passive"))
      (node (ref "X16") (pin "1") (pinfunction "S_1") (pintype "passive"))
      (node (ref "X17") (pin "1") (pinfunction "S_1") (pintype "passive"))
      (node (ref "X18") (pin "1") (pinfunction "S_1") (pintype "passive"))
      (node (ref "X19") (pin "1") (pinfunction "S_1") (pintype "passive"))
      (node (ref "X2") (pin "2") (pinfunction "1_2") (pintype "passive"))
      (node (ref "X20") (pin "1") (pinfunction "S_1") (pintype "passive"))
      (node (ref "X21") (pin "1") (pinfunction "S_1") (pintype "passive"))
      (node (ref "X22") (pin "1") (pinfunction "S_1") (pintype "passive"))
      (node (ref "X23") (pin "1") (pinfunction "S_1") (pintype "passive"))
      (node (ref "X24") (pin "1") (pinfunction "S_1") (pintype "passive"))
      (node (ref "X25") (pin "1") (pinfunction "S_1") (pintype "passive"))
      (node (ref "X26") (pin "1") (pinfunction "S_1") (pintype "passive"))
      (node (ref "X27") (pin "1") (pinfunction "S_1") (pintype "passive"))
      (node (ref "X28") (pin "1") (pinfunction "S_1") (pintype "passive"))
      (node (ref "X29") (pin "1") (pinfunction "S_1") (pintype "passive"))
      (node (ref "X3") (pin "2") (pinfunction "1_2") (pintype "passive"))
      (node (ref "X30") (pin "1") (pinfunction "S_1") (pintype "passive"))
      (node (ref "X31") (pin "1") (pinfunction "S_1") (pintype "passive"))
      (node (ref "X32") (pin "1") (pinfunction "S_1") (pintype "passive"))
      (node (ref "X33") (pin "1") (pinfunction "S_1") (pintype "passive"))
      (node (ref "X4") (pin "4") (pinfunction "1_4") (pintype "passive"))
      (node (ref "X5") (pin "1") (pinfunction "S_1") (pintype "passive"))
      (node (ref "X7") (pin "1") (pinfunction "S_1") (pintype "passive"))
      (node (ref "X8") (pin "1") (pinfunction "S_1") (pintype "passive"))
    )
    (net (code "10") (name "IO0") (class "Default")
      (node (ref "C7") (pin "1") (pinfunction "1_1") (pintype "passive"))
      (node (ref "Q3") (pin "3") (pinfunction "C_3") (pintype "passive"))
      (node (ref "R4") (pin "1") (pinfunction "1_1") (pintype "passive"))
      (node (ref "S2") (pin "1") (pinfunction "1_1") (pintype "passive"))
      (node (ref "U3") (pin "25") (pinfunction "IO0_25") (pintype "bidirectional"))
    )
    (net (code "11") (name "M1") (class "Default")
      (node (ref "EBYTEE220-900T22D1") (pin "M1") (pinfunction "M1_M1") (pintype "bidirectional"))
      (node (ref "U3") (pin "29") (pinfunction "IO5_29") (pintype "bidirectional"))
    )
    (net (code "12") (name "Net-(D3-PadA)") (class "Default")
      (node (ref "D3") (pin "A") (pinfunction "A_A") (pintype "passive"))
      (node (ref "X2") (pin "1") (pinfunction "1_1") (pintype "passive"))
    )
    (net (code "13") (name "Net-(D5-K)") (class "Default")
      (node (ref "D5") (pin "C") (pinfunction "K_C") (pintype "passive"))
      (node (ref "U3") (pin "28") (pinfunction "IO17_28") (pintype "bidirectional"))
    )
    (net (code "14") (name "Net-(D7-K)") (class "Default")
      (node (ref "D7") (pin "C") (pinfunction "K_C") (pintype "passive"))
      (node (ref "EBYTEE220-900T22D1") (pin "TXD") (pinfunction "TXD_TXD") (pintype "bidirectional"))
    )
    (net (code "15") (name "Net-(IC1-A0)") (class "Default")
      (node (ref "IC1") (pin "15") (pinfunction "A0_15") (pintype "input"))
      (node (ref "R62") (pin "1") (pinfunction "1_1") (pintype "passive"))
    )
    (net (code "16") (name "Net-(IC1-A1)") (class "Default")
      (node (ref "IC1") (pin "16") (pinfunction "A1_16") (pintype "input"))
      (node (ref "R63") (pin "1") (pinfunction "1_1") (pintype "passive"))
    )
    (net (code "17") (name "Net-(IC1-A2)") (class "Default")
      (node (ref "IC1") (pin "17") (pinfunction "A2_17") (pintype "input"))
      (node (ref "R64") (pin "1") (pinfunction "1_1") (pintype "passive"))
    )
    (net (code "18") (name "Net-(IC1-~{RESET})") (class "Default")
      (node (ref "IC1") (pin "18") (pinfunction "~{RESET}_18") (pintype "input"))
      (node (ref "R59") (pin "1") (pinfunction "1_1") (pintype "passive"))
    )
    (net (code "19") (name "Net-(IC2-A0)") (class "Default")
      (node (ref "IC2") (pin "15") (pinfunction "A0_15") (pintype "input"))
      (node (ref "R68") (pin "1") (pinfunction "1_1") (pintype "passive"))
    )
    (net (code "20") (name "Net-(IC2-A1)") (class "Default")
      (node (ref "IC2") (pin "16") (pinfunction "A1_16") (pintype "input"))
      (node (ref "R69") (pin "1") (pinfunction "1_1") (pintype "passive"))
    )
    (net (code "21") (name "Net-(IC2-A2)") (class "Default")
      (node (ref "IC2") (pin "17") (pinfunction "A2_17") (pintype "input"))
      (node (ref "R70") (pin "1") (pinfunction "1_1") (pintype "passive"))
    )
    (net (code "22") (name "Net-(IC2-~{RESET})") (class "Default")
      (node (ref "IC2") (pin "18") (pinfunction "~{RESET}_18") (pintype "input"))
      (node (ref "R65") (pin "1") (pinfunction "1_1") (pintype "passive"))
    )
    (net (code "23") (name "Net-(PS1-AC(L))") (class "Default")
      (node (ref "PS1") (pin "1") (pinfunction "AC(L)_1") (pintype "input"))
      (node (ref "X1") (pin "1") (pinfunction "1_1") (pintype "passive"))
    )
    (net (code "24") (name "Net-(PS1-AC(N))") (class "Default")
      (node (ref "PS1") (pin "2") (pinfunction "AC(N)_2") (pintype "input"))
      (node (ref "X1") (pin "2") (pinfunction "1_2") (pintype "passive"))
    )
    (net (code "25") (name "Net-(Q2-B)") (class "Default")
      (node (ref "Q2") (pin "1") (pinfunction "B_1") (pintype "passive"))
      (node (ref "R1") (pin "2") (pinfunction "2_2") (pintype "passive"))
    )
    (net (code "26") (name "Net-(Q3-B)") (class "Default")
      (node (ref "Q3") (pin "1") (pinfunction "B_1") (pintype "passive"))
      (node (ref "R2") (pin "2") (pinfunction "2_2") (pintype "passive"))
    )
    (net (code "27") (name "Net-(Q5-PadB)") (class "Default")
      (node (ref "Q5") (pin "B") (pinfunction "B_B") (pintype "passive"))
      (node (ref "R12") (pin "2") (pinfunction "2_2") (pintype "passive"))
    )
    (net (code "28") (name "Net-(Q6-PadB)") (class "Default")
      (node (ref "Q6") (pin "B") (pinfunction "B_B") (pintype "passive"))
      (node (ref "R14") (pin "2") (pinfunction "2_2") (pintype "passive"))
    )
    (net (code "29") (name "Net-(Q7-PadB)") (class "Default")
      (node (ref "Q7") (pin "B") (pinfunction "B_B") (pintype "passive"))
      (node (ref "R16") (pin "2") (pinfunction "2_2") (pintype "passive"))
    )
    (net (code "30") (name "Net-(Q8-PadB)") (class "Default")
      (node (ref "Q8") (pin "B") (pinfunction "B_B") (pintype "passive"))
      (node (ref "R18") (pin "2") (pinfunction "2_2") (pintype "passive"))
    )
    (net (code "31") (name "Net-(Q9-PadB)") (class "Default")
      (node (ref "Q9") (pin "B") (pinfunction "B_B") (pintype "passive"))
      (node (ref "R20") (pin "2") (pinfunction "2_2") (pintype "passive"))
    )
    (net (code "32") (name "Net-(Q10-PadB)") (class "Default")
      (node (ref "Q10") (pin "B") (pinfunction "B_B") (pintype "passive"))
      (node (ref "R22") (pin "2") (pinfunction "2_2") (pintype "passive"))
    )
    (net (code "33") (name "Net-(Q11-PadB)") (class "Default")
      (node (ref "Q11") (pin "B") (pinfunction "B_B") (pintype "passive"))
      (node (ref "R24") (pin "2") (pinfunction "2_2") (pintype "passive"))
    )
    (net (code "34") (name "Net-(Q12-PadB)") (class "Default")
      (node (ref "Q12") (pin "B") (pinfunction "B_B") (pintype "passive"))
      (node (ref "R26") (pin "2") (pinfunction "2_2") (pintype "passive"))
    )
    (net (code "35") (name "Net-(Q13-PadB)") (class "Default")
      (node (ref "Q13") (pin "B") (pinfunction "B_B") (pintype "passive"))
      (node (ref "R28") (pin "2") (pinfunction "2_2") (pintype "passive"))
    )
    (net (code "36") (name "Net-(Q14-PadB)") (class "Default")
      (node (ref "Q14") (pin "B") (pinfunction "B_B") (pintype "passive"))
      (node (ref "R30") (pin "2") (pinfunction "2_2") (pintype "passive"))
    )
    (net (code "37") (name "Net-(Q15-PadB)") (class "Default")
      (node (ref "Q15") (pin "B") (pinfunction "B_B") (pintype "passive"))
      (node (ref "R32") (pin "2") (pinfunction "2_2") (pintype "passive"))
    )
    (net (code "38") (name "Net-(Q16-PadB)") (class "Default")
      (node (ref "Q16") (pin "B") (pinfunction "B_B") (pintype "passive"))
      (node (ref "R34") (pin "2") (pinfunction "2_2") (pintype "passive"))
    )
    (net (code "39") (name "Net-(Q17-PadB)") (class "Default")
      (node (ref "Q17") (pin "B") (pinfunction "B_B") (pintype "passive"))
      (node (ref "R36") (pin "2") (pinfunction "2_2") (pintype "passive"))
    )
    (net (code "40") (name "Net-(Q18-PadB)") (class "Default")
      (node (ref "Q18") (pin "B") (pinfunction "B_B") (pintype "passive"))
      (node (ref "R38") (pin "2") (pinfunction "2_2") (pintype "passive"))
    )
    (net (code "41") (name "Net-(Q19-PadB)") (class "Default")
      (node (ref "Q19") (pin "B") (pinfunction "B_B") (pintype "passive"))
      (node (ref "R40") (pin "2") (pinfunction "2_2") (pintype "passive"))
    )
    (net (code "42") (name "Net-(Q20-PadB)") (class "Default")
      (node (ref "Q20") (pin "B") (pinfunction "B_B") (pintype "passive"))
      (node (ref "R42") (pin "2") (pinfunction "2_2") (pintype "passive"))
    )
    (net (code "43") (name "Net-(Q21-PadB)") (class "Default")
      (node (ref "Q21") (pin "B") (pinfunction "B_B") (pintype "passive"))
      (node (ref "R44") (pin "2") (pinfunction "2_2") (pintype "passive"))
    )
    (net (code "44") (name "Net-(Q22-PadB)") (class "Default")
      (node (ref "Q22") (pin "B") (pinfunction "B_B") (pintype "passive"))
      (node (ref "R46") (pin "2") (pinfunction "2_2") (pintype "passive"))
    )
    (net (code "45") (name "Net-(Q23-PadB)") (class "Default")
      (node (ref "Q23") (pin "B") (pinfunction "B_B") (pintype "passive"))
      (node (ref "R48") (pin "2") (pinfunction "2_2") (pintype "passive"))
    )
    (net (code "46") (name "Net-(Q24-PadB)") (class "Default")
      (node (ref "Q24") (pin "B") (pinfunction "B_B") (pintype "passive"))
      (node (ref "R50") (pin "2") (pinfunction "2_2") (pintype "passive"))
    )
    (net (code "47") (name "Net-(Q25-PadB)") (class "Default")
      (node (ref "Q25") (pin "B") (pinfunction "B_B") (pintype "passive"))
      (node (ref "R52") (pin "2") (pinfunction "2_2") (pintype "passive"))
    )
    (net (code "48") (name "Net-(Q26-PadB)") (class "Default")
      (node (ref "Q26") (pin "B") (pinfunction "B_B") (pintype "passive"))
      (node (ref "R54") (pin "2") (pinfunction "2_2") (pintype "passive"))
    )
    (net (code "49") (name "Net-(Q27-PadB)") (class "Default")
      (node (ref "Q27") (pin "B") (pinfunction "B_B") (pintype "passive"))
      (node (ref "R56") (pin "2") (pinfunction "2_2") (pintype "passive"))
    )
    (net (code "50") (name "Net-(Q28-PadB)") (class "Default")
      (node (ref "Q28") (pin "B") (pinfunction "B_B") (pintype "passive"))
      (node (ref "R58") (pin "2") (pinfunction "2_2") (pintype "passive"))
    )
    (net (code "51") (name "Net-(U1-V3)") (class "Default")
      (node (ref "C5") (pin "1") (pinfunction "1_1") (pintype "passive"))
      (node (ref "U1") (pin "4") (pinfunction "V3_4") (pintype "power_in"))
    )
    (net (code "52") (name "Net-(U1-XI)") (class "Default")
      (node (ref "C1") (pin "2") (pinfunction "2_2") (pintype "passive"))
      (node (ref "Q1") (pin "2") (pinfunction "2_2") (pintype "passive"))
      (node (ref "U1") (pin "7") (pinfunction "XI_7") (pintype "input"))
    )
    (net (code "53") (name "Net-(U1-XO)") (class "Default")
      (node (ref "C2") (pin "2") (pinfunction "2_2") (pintype "passive"))
      (node (ref "Q1") (pin "1") (pinfunction "1_1") (pintype "passive"))
      (node (ref "U1") (pin "8") (pinfunction "XO_8") (pintype "output"))
    )
    (net (code "54") (name "Net-(X8B-S)") (class "Default")
      (node (ref "D4") (pin "A") (pinfunction "A_A") (pintype "passive"))
      (node (ref "X8") (pin "2") (pinfunction "S_2") (pintype "passive"))
    )
    (net (code "55") (name "Net-(X10B-S)") (class "Default")
      (node (ref "Q5") (pin "E") (pinfunction "E_E") (pintype "passive"))
      (node (ref "X10") (pin "2") (pinfunction "S_2") (pintype "passive"))
    )
    (net (code "56") (name "Net-(X11B-S)") (class "Default")
      (node (ref "Q6") (pin "E") (pinfunction "E_E") (pintype "passive"))
      (node (ref "X11") (pin "2") (pinfunction "S_2") (pintype "passive"))
    )
    (net (code "57") (name "Net-(X12B-S)") (class "Default")
      (node (ref "Q7") (pin "E") (pinfunction "E_E") (pintype "passive"))
      (node (ref "X12") (pin "2") (pinfunction "S_2") (pintype "passive"))
    )
    (net (code "58") (name "Net-(X13B-S)") (class "Default")
      (node (ref "Q8") (pin "E") (pinfunction "E_E") (pintype "passive"))
      (node (ref "X13") (pin "2") (pinfunction "S_2") (pintype "passive"))
    )
    (net (code "59") (name "Net-(X14B-S)") (class "Default")
      (node (ref "Q9") (pin "E") (pinfunction "E_E") (pintype "passive"))
      (node (ref "X14") (pin "2") (pinfunction "S_2") (pintype "passive"))
    )
    (net (code "60") (name "Net-(X15B-S)") (class "Default")
      (node (ref "Q10") (pin "E") (pinfunction "E_E") (pintype "passive"))
      (node (ref "X15") (pin "2") (pinfunction "S_2") (pintype "passive"))
    )
    (net (code "61") (name "Net-(X16B-S)") (class "Default")
      (node (ref "Q11") (pin "E") (pinfunction "E_E") (pintype "passive"))
      (node (ref "X16") (pin "2") (pinfunction "S_2") (pintype "passive"))
    )
    (net (code "62") (name "Net-(X17B-S)") (class "Default")
      (node (ref "Q12") (pin "E") (pinfunction "E_E") (pintype "passive"))
      (node (ref "X17") (pin "2") (pinfunction "S_2") (pintype "passive"))
    )
    (net (code "63") (name "Net-(X18B-S)") (class "Default")
      (node (ref "Q13") (pin "E") (pinfunction "E_E") (pintype "passive"))
      (node (ref "X18") (pin "2") (pinfunction "S_2") (pintype "passive"))
    )
    (net (code "64") (name "Net-(X19B-S)") (class "Default")
      (node (ref "Q14") (pin "E") (pinfunction "E_E") (pintype "passive"))
      (node (ref "X19") (pin "2") (pinfunction "S_2") (pintype "passive"))
    )
    (net (code "65") (name "Net-(X20B-S)") (class "Default")
      (node (ref "Q15") (pin "E") (pinfunction "E_E") (pintype "passive"))
      (node (ref "X20") (pin "2") (pinfunction "S_2") (pintype "passive"))
    )
    (net (code "66") (name "Net-(X21B-S)") (class "Default")
      (node (ref "Q16") (pin "E") (pinfunction "E_E") (pintype "passive"))
      (node (ref "X21") (pin "2") (pinfunction "S_2") (pintype "passive"))
    )
    (net (code "67") (name "Net-(X22B-S)") (class "Default")
      (node (ref "Q17") (pin "E") (pinfunction "E_E") (pintype "passive"))
      (node (ref "X22") (pin "2") (pinfunction "S_2") (pintype "passive"))
    )
    (net (code "68") (name "Net-(X23B-S)") (class "Default")
      (node (ref "Q18") (pin "E") (pinfunction "E_E") (pintype "passive"))
      (node (ref "X23") (pin "2") (pinfunction "S_2") (pintype "passive"))
    )
    (net (code "69") (name "Net-(X24B-S)") (class "Default")
      (node (ref "Q19") (pin "E") (pinfunction "E_E") (pintype "passive"))
      (node (ref "X24") (pin "2") (pinfunction "S_2") (pintype "passive"))
    )
    (net (code "70") (name "Net-(X25B-S)") (class "Default")
      (node (ref "Q20") (pin "E") (pinfunction "E_E") (pintype "passive"))
      (node (ref "X25") (pin "2") (pinfunction "S_2") (pintype "passive"))
    )
    (net (code "71") (name "Net-(X26B-S)") (class "Default")
      (node (ref "Q21") (pin "E") (pinfunction "E_E") (pintype "passive"))
      (node (ref "X26") (pin "2") (pinfunction "S_2") (pintype "passive"))
    )
    (net (code "72") (name "Net-(X27B-S)") (class "Default")
      (node (ref "Q22") (pin "E") (pinfunction "E_E") (pintype "passive"))
      (node (ref "X27") (pin "2") (pinfunction "S_2") (pintype "passive"))
    )
    (net (code "73") (name "Net-(X28B-S)") (class "Default")
      (node (ref "Q23") (pin "E") (pinfunction "E_E") (pintype "passive"))
      (node (ref "X28") (pin "2") (pinfunction "S_2") (pintype "passive"))
    )
    (net (code "74") (name "Net-(X29B-S)") (class "Default")
      (node (ref "Q24") (pin "E") (pinfunction "E_E") (pintype "passive"))
      (node (ref "X29") (pin "2") (pinfunction "S_2") (pintype "passive"))
    )
    (net (code "75") (name "Net-(X30B-S)") (class "Default")
      (node (ref "Q25") (pin "E") (pinfunction "E_E") (pintype "passive"))
      (node (ref "X30") (pin "2") (pinfunction "S_2") (pintype "passive"))
    )
    (net (code "76") (name "Net-(X31B-S)") (class "Default")
      (node (ref "Q26") (pin "E") (pinfunction "E_E") (pintype "passive"))
      (node (ref "X31") (pin "2") (pinfunction "S_2") (pintype "passive"))
    )
    (net (code "77") (name "Net-(X32B-S)") (class "Default")
      (node (ref "Q27") (pin "E") (pinfunction "E_E") (pintype "passive"))
      (node (ref "X32") (pin "2") (pinfunction "S_2") (pintype "passive"))
    )
    (net (code "78") (name "Net-(X33B-S)") (class "Default")
      (node (ref "Q28") (pin "E") (pinfunction "E_E") (pintype "passive"))
      (node (ref "X33") (pin "2") (pinfunction "S_2") (pintype "passive"))
    )
    (net (code "79") (name "O1") (class "Default")
      (node (ref "IC1") (pin "21") (pinfunction "GPA0_21") (pintype "bidirectional"))
      (node (ref "Q5") (pin "C") (pinfunction "C_C") (pintype "passive"))
      (node (ref "R11") (pin "2") (pinfunction "2_2") (pintype "passive"))
    )
    (net (code "80") (name "O2") (class "Default")
      (node (ref "IC1") (pin "22") (pinfunction "GPA1_22") (pintype "bidirectional"))
      (node (ref "Q6") (pin "C") (pinfunction "C_C") (pintype "passive"))
      (node (ref "R13") (pin "2") (pinfunction "2_2") (pintype "passive"))
    )
    (net (code "81") (name "O3") (class "Default")
      (node (ref "IC1") (pin "23") (pinfunction "GPA2_23") (pintype "bidirectional"))
      (node (ref "Q7") (pin "C") (pinfunction "C_C") (pintype "passive"))
      (node (ref "R15") (pin "2") (pinfunction "2_2") (pintype "passive"))
    )
    (net (code "82") (name "O4") (class "Default")
      (node (ref "IC1") (pin "24") (pinfunction "GPA3_24") (pintype "bidirectional"))
      (node (ref "Q8") (pin "C") (pinfunction "C_C") (pintype "passive"))
      (node (ref "R17") (pin "2") (pinfunction "2_2") (pintype "passive"))
    )
    (net (code "83") (name "O5") (class "Default")
      (node (ref "IC1") (pin "25") (pinfunction "GPA4_25") (pintype "bidirectional"))
      (node (ref "Q9") (pin "C") (pinfunction "C_C") (pintype "passive"))
      (node (ref "R19") (pin "2") (pinfunction "2_2") (pintype "passive"))
    )
    (net (code "84") (name "O6") (class "Default")
      (node (ref "IC1") (pin "26") (pinfunction "GPA5_26") (pintype "bidirectional"))
      (node (ref "Q10") (pin "C") (pinfunction "C_C") (pintype "passive"))
      (node (ref "R21") (pin "2") (pinfunction "2_2") (pintype "passive"))
    )
    (net (code "85") (name "O7") (class "Default")
      (node (ref "IC1") (pin "27") (pinfunction "GPA6_27") (pintype "bidirectional"))
      (node (ref "Q11") (pin "C") (pinfunction "C_C") (pintype "passive"))
      (node (ref "R23") (pin "2") (pinfunction "2_2") (pintype "passive"))
    )
    (net (code "86") (name "O8") (class "Default")
      (node (ref "IC1") (pin "28") (pinfunction "GPA7_28") (pintype "bidirectional"))
      (node (ref "Q12") (pin "C") (pinfunction "C_C") (pintype "passive"))
      (node (ref "R25") (pin "2") (pinfunction "2_2") (pintype "passive"))
    )
    (net (code "87") (name "O9") (class "Default")
      (node (ref "IC1") (pin "1") (pinfunction "GPB0_1") (pintype "bidirectional"))
      (node (ref "Q13") (pin "C") (pinfunction "C_C") (pintype "passive"))
      (node (ref "R27") (pin "2") (pinfunction "2_2") (pintype "passive"))
    )
    (net (code "88") (name "O10") (class "Default")
      (node (ref "IC1") (pin "2") (pinfunction "GPB1_2") (pintype "bidirectional"))
      (node (ref "Q14") (pin "C") (pinfunction "C_C") (pintype "passive"))
      (node (ref "R29") (pin "2") (pinfunction "2_2") (pintype "passive"))
    )
    (net (code "89") (name "O11") (class "Default")
      (node (ref "IC1") (pin "3") (pinfunction "GPB2_3") (pintype "bidirectional"))
      (node (ref "Q15") (pin "C") (pinfunction "C_C") (pintype "passive"))
      (node (ref "R31") (pin "2") (pinfunction "2_2") (pintype "passive"))
    )
    (net (code "90") (name "O12") (class "Default")
      (node (ref "IC1") (pin "4") (pinfunction "GPB3_4") (pintype "bidirectional"))
      (node (ref "Q16") (pin "C") (pinfunction "C_C") (pintype "passive"))
      (node (ref "R33") (pin "2") (pinfunction "2_2") (pintype "passive"))
    )
    (net (code "91") (name "O13") (class "Default")
      (node (ref "IC1") (pin "5") (pinfunction "GPB4_5") (pintype "bidirectional"))
      (node (ref "Q17") (pin "C") (pinfunction "C_C") (pintype "passive"))
      (node (ref "R35") (pin "2") (pinfunction "2_2") (pintype "passive"))
    )
    (net (code "92") (name "O14") (class "Default")
      (node (ref "IC1") (pin "6") (pinfunction "GPB5_6") (pintype "bidirectional"))
      (node (ref "Q18") (pin "C") (pinfunction "C_C") (pintype "passive"))
      (node (ref "R37") (pin "2") (pinfunction "2_2") (pintype "passive"))
    )
    (net (code "93") (name "O15") (class "Default")
      (node (ref "IC1") (pin "7") (pinfunction "GPB6_7") (pintype "bidirectional"))
      (node (ref "Q19") (pin "C") (pinfunction "C_C") (pintype "passive"))
      (node (ref "R39") (pin "2") (pinfunction "2_2") (pintype "passive"))
    )
    (net (code "94") (name "O16") (class "Default")
      (node (ref "IC1") (pin "8") (pinfunction "GPB7_8") (pintype "bidirectional"))
      (node (ref "Q20") (pin "C") (pinfunction "C_C") (pintype "passive"))
      (node (ref "R41") (pin "2") (pinfunction "2_2") (pintype "passive"))
    )
    (net (code "95") (name "O17") (class "Default")
      (node (ref "IC2") (pin "21") (pinfunction "GPA0_21") (pintype "bidirectional"))
      (node (ref "Q21") (pin "C") (pinfunction "C_C") (pintype "passive"))
      (node (ref "R43") (pin "2") (pinfunction "2_2") (pintype "passive"))
    )
    (net (code "96") (name "O18") (class "Default")
      (node (ref "IC2") (pin "22") (pinfunction "GPA1_22") (pintype "bidirectional"))
      (node (ref "Q22") (pin "C") (pinfunction "C_C") (pintype "passive"))
      (node (ref "R45") (pin "2") (pinfunction "2_2") (pintype "passive"))
    )
    (net (code "97") (name "O19") (class "Default")
      (node (ref "IC2") (pin "23") (pinfunction "GPA2_23") (pintype "bidirectional"))
      (node (ref "Q23") (pin "C") (pinfunction "C_C") (pintype "passive"))
      (node (ref "R47") (pin "2") (pinfunction "2_2") (pintype "passive"))
    )
    (net (code "98") (name "O20") (class "Default")
      (node (ref "IC2") (pin "24") (pinfunction "GPA3_24") (pintype "bidirectional"))
      (node (ref "Q24") (pin "C") (pinfunction "C_C") (pintype "passive"))
      (node (ref "R49") (pin "2") (pinfunction "2_2") (pintype "passive"))
    )
    (net (code "99") (name "O21") (class "Default")
      (node (ref "IC2") (pin "25") (pinfunction "GPA4_25") (pintype "bidirectional"))
      (node (ref "Q25") (pin "C") (pinfunction "C_C") (pintype "passive"))
      (node (ref "R51") (pin "2") (pinfunction "2_2") (pintype "passive"))
    )
    (net (code "100") (name "O22") (class "Default")
      (node (ref "IC2") (pin "26") (pinfunction "GPA5_26") (pintype "bidirectional"))
      (node (ref "Q26") (pin "C") (pinfunction "C_C") (pintype "passive"))
      (node (ref "R53") (pin "2") (pinfunction "2_2") (pintype "passive"))
    )
    (net (code "101") (name "O23") (class "Default")
      (node (ref "IC2") (pin "27") (pinfunction "GPA6_27") (pintype "bidirectional"))
      (node (ref "Q27") (pin "C") (pinfunction "C_C") (pintype "passive"))
      (node (ref "R55") (pin "2") (pinfunction "2_2") (pintype "passive"))
    )
    (net (code "102") (name "O24") (class "Default")
      (node (ref "IC2") (pin "28") (pinfunction "GPA7_28") (pintype "bidirectional"))
      (node (ref "Q28") (pin "C") (pinfunction "C_C") (pintype "passive"))
      (node (ref "R57") (pin "2") (pinfunction "2_2") (pintype "passive"))
    )
    (net (code "103") (name "ROTATY-CCW") (class "Default")
      (node (ref "R6") (pin "1") (pinfunction "1_1") (pintype "passive"))
      (node (ref "U3") (pin "23") (pinfunction "IO15_23") (pintype "bidirectional"))
      (node (ref "X5") (pin "2") (pinfunction "S_2") (pintype "passive"))
    )
    (net (code "104") (name "ROTATY-CW") (class "Default")
      (node (ref "R5") (pin "1") (pinfunction "1_1") (pintype "passive"))
      (node (ref "U3") (pin "13") (pinfunction "IO14_13") (pintype "bidirectional"))
      (node (ref "X5") (pin "3") (pinfunction "S_3") (pintype "passive"))
    )
    (net (code "105") (name "RTS") (class "Default")
      (node (ref "Q2") (pin "2") (pinfunction "E_2") (pintype "passive"))
      (node (ref "R2") (pin "1") (pinfunction "1_1") (pintype "passive"))
      (node (ref "U1") (pin "14") (pinfunction "~{RTS}_14") (pintype "output"))
    )
    (net (code "106") (name "RX") (class "Default")
      (node (ref "U1") (pin "3") (pinfunction "RXD_3") (pintype "input"))
      (node (ref "U3") (pin "35") (pinfunction "TXD0_35") (pintype "bidirectional"))
    )
    (net (code "107") (name "RX_LORA") (class "Default")
      (node (ref "D5") (pin "A") (pinfunction "A_A") (pintype "passive"))
      (node (ref "EBYTEE220-900T22D1") (pin "RXD") (pinfunction "RXD_RXD") (pintype "bidirectional"))
      (node (ref "R7") (pin "1") (pinfunction "1_1") (pintype "passive"))
    )
    (net (code "108") (name "RX_RS485") (class "Default")
      (node (ref "TTL-RS1") (pin "RX") (pinfunction "RX_RX") (pintype "bidirectional"))
      (node (ref "U3") (pin "31") (pinfunction "IO19_31") (pintype "bidirectional"))
    )
    (net (code "109") (name "SCL") (class "Default")
      (node (ref "IC1") (pin "12") (pinfunction "SCL_12") (pintype "input"))
      (node (ref "IC2") (pin "12") (pinfunction "SCL_12") (pintype "input"))
      (node (ref "R60") (pin "1") (pinfunction "1_1") (pintype "passive"))
      (node (ref "R66") (pin "1") (pinfunction "1_1") (pintype "passive"))
      (node (ref "U3") (pin "36") (pinfunction "IO22_36") (pintype "bidirectional"))
    )
    (net (code "110") (name "SDA") (class "Default")
      (node (ref "IC1") (pin "13") (pinfunction "SDA_13") (pintype "bidirectional"))
      (node (ref "IC2") (pin "13") (pinfunction "SDA_13") (pintype "bidirectional"))
      (node (ref "R61") (pin "2") (pinfunction "2_2") (pintype "passive"))
      (node (ref "R67") (pin "2") (pinfunction "2_2") (pintype "passive"))
      (node (ref "U3") (pin "33") (pinfunction "IO21_33") (pintype "bidirectional"))
    )
    (net (code "111") (name "TX") (class "Default")
      (node (ref "U1") (pin "2") (pinfunction "TXD_2") (pintype "output"))
      (node (ref "U3") (pin "34") (pinfunction "RXD0_34") (pintype "bidirectional"))
    )
    (net (code "112") (name "TX_LORA") (class "Default")
      (node (ref "D7") (pin "A") (pinfunction "A_A") (pintype "passive"))
      (node (ref "R8") (pin "1") (pinfunction "1_1") (pintype "passive"))
      (node (ref "U3") (pin "27") (pinfunction "IO16_27") (pintype "bidirectional"))
    )
    (net (code "113") (name "TX_RS485") (class "Default")
      (node (ref "TTL-RS1") (pin "TX") (pinfunction "TX_TX") (pintype "bidirectional"))
      (node (ref "U3") (pin "30") (pinfunction "IO18_30") (pintype "bidirectional"))
    )
    (net (code "114") (name "USB_N") (class "Default")
      (node (ref "J1") (pin "2") (pinfunction "D-_2") (pintype "passive"))
      (node (ref "U1") (pin "6") (pinfunction "UD-_6") (pintype "bidirectional"))
    )
    (net (code "115") (name "USB_P") (class "Default")
      (node (ref "J1") (pin "3") (pinfunction "D+_3") (pintype "passive"))
      (node (ref "U1") (pin "5") (pinfunction "UD+_5") (pintype "bidirectional"))
    )
    (net (code "116") (name "VCC") (class "Default")
      (node (ref "C9") (pin "2") (pinfunction "2_2") (pintype "passive"))
      (node (ref "R3") (pin "2") (pinfunction "2_2") (pintype "passive"))
      (node (ref "R4") (pin "2") (pinfunction "2_2") (pintype "passive"))
      (node (ref "R7") (pin "2") (pinfunction "2_2") (pintype "passive"))
      (node (ref "R8") (pin "2") (pinfunction "2_2") (pintype "passive"))
      (node (ref "U2") (pin "2") (pinfunction "VOUT_2") (pintype "output"))
      (node (ref "U2") (pin "4") (pinfunction "VOUT_4") (pintype "output"))
      (node (ref "U3") (pin "2") (pinfunction "3V3_2") (pintype "power_in"))
    )
    (net (code "117") (name "VUSB") (class "Default")
      (node (ref "C3") (pin "+") (pinfunction "+_+") (pintype "passive"))
      (node (ref "C4") (pin "1") (pinfunction "1_1") (pintype "passive"))
      (node (ref "D8") (pin "A") (pinfunction "A_A") (pintype "passive"))
      (node (ref "J1") (pin "1") (pinfunction "VUSB_1") (pintype "passive"))
      (node (ref "U1") (pin "16") (pinfunction "VCC_16") (pintype "power_in"))
    )
    (net (code "118") (name "unconnected-(EBYTEE220-900T22D1-PadAUX)") (class "Default")
      (node (ref "EBYTEE220-900T22D1") (pin "AUX") (pinfunction "AUX_AUX") (pintype "bidirectional"))
    )
    (net (code "119") (name "unconnected-(IC1-INTA-Pad20)") (class "Default")
      (node (ref "IC1") (pin "20") (pinfunction "INTA_20") (pintype "output"))
    )
    (net (code "120") (name "unconnected-(IC1-INTB-Pad19)") (class "Default")
      (node (ref "IC1") (pin "19") (pinfunction "INTB_19") (pintype "output"))
    )
    (net (code "121") (name "unconnected-(IC2-GPB0-Pad1)") (class "Default")
      (node (ref "IC2") (pin "1") (pinfunction "GPB0_1") (pintype "bidirectional"))
    )
    (net (code "122") (name "unconnected-(IC2-GPB1-Pad2)") (class "Default")
      (node (ref "IC2") (pin "2") (pinfunction "GPB1_2") (pintype "bidirectional"))
    )
    (net (code "123") (name "unconnected-(IC2-GPB2-Pad3)") (class "Default")
      (node (ref "IC2") (pin "3") (pinfunction "GPB2_3") (pintype "bidirectional"))
    )
    (net (code "124") (name "unconnected-(IC2-GPB3-Pad4)") (class "Default")
      (node (ref "IC2") (pin "4") (pinfunction "GPB3_4") (pintype "bidirectional"))
    )
    (net (code "125") (name "unconnected-(IC2-GPB4-Pad5)") (class "Default")
      (node (ref "IC2") (pin "5") (pinfunction "GPB4_5") (pintype "bidirectional"))
    )
    (net (code "126") (name "unconnected-(IC2-GPB5-Pad6)") (class "Default")
      (node (ref "IC2") (pin "6") (pinfunction "GPB5_6") (pintype "bidirectional"))
    )
    (net (code "127") (name "unconnected-(IC2-GPB6-Pad7)") (class "Default")
      (node (ref "IC2") (pin "7") (pinfunction "GPB6_7") (pintype "bidirectional"))
    )
    (net (code "128") (name "unconnected-(IC2-GPB7-Pad8)") (class "Default")
      (node (ref "IC2") (pin "8") (pinfunction "GPB7_8") (pintype "bidirectional"))
    )
    (net (code "129") (name "unconnected-(IC2-INTA-Pad20)") (class "Default")
      (node (ref "IC2") (pin "20") (pinfunction "INTA_20") (pintype "output"))
    )
    (net (code "130") (name "unconnected-(IC2-INTB-Pad19)") (class "Default")
      (node (ref "IC2") (pin "19") (pinfunction "INTB_19") (pintype "output"))
    )
    (net (code "131") (name "unconnected-(J1-ID-Pad4)") (class "Default")
      (node (ref "J1") (pin "4") (pinfunction "ID_4") (pintype "passive"))
    )
    (net (code "132") (name "unconnected-(U1-RS232-Pad15)") (class "Default")
      (node (ref "U1") (pin "15") (pinfunction "RS232_15") (pintype "input"))
    )
    (net (code "133") (name "unconnected-(U1-~{CTS}-Pad9)") (class "Default")
      (node (ref "U1") (pin "9") (pinfunction "~{CTS}_9") (pintype "input"))
    )
    (net (code "134") (name "unconnected-(U1-~{DCD}-Pad12)") (class "Default")
      (node (ref "U1") (pin "12") (pinfunction "~{DCD}_12") (pintype "input"))
    )
    (net (code "135") (name "unconnected-(U1-~{DSR}-Pad10)") (class "Default")
      (node (ref "U1") (pin "10") (pinfunction "~{DSR}_10") (pintype "input"))
    )
    (net (code "136") (name "unconnected-(U1-~{RI}-Pad11)") (class "Default")
      (node (ref "U1") (pin "11") (pinfunction "~{RI}_11") (pintype "input"))
    )
    (net (code "137") (name "unconnected-(U3-IO2-Pad24)") (class "Default")
      (node (ref "U3") (pin "24") (pinfunction "IO2_24") (pintype "bidirectional"))
    )
    (net (code "138") (name "unconnected-(U3-IO4-Pad26)") (class "Default")
      (node (ref "U3") (pin "26") (pinfunction "IO4_26") (pintype "bidirectional"))
    )
    (net (code "139") (name "unconnected-(U3-IO12-Pad14)") (class "Default")
      (node (ref "U3") (pin "14") (pinfunction "IO12_14") (pintype "bidirectional"))
    )
    (net (code "140") (name "unconnected-(U3-IO13-Pad16)") (class "Default")
      (node (ref "U3") (pin "16") (pinfunction "IO13_16") (pintype "bidirectional"))
    )
    (net (code "141") (name "unconnected-(U3-IO23-Pad37)") (class "Default")
      (node (ref "U3") (pin "37") (pinfunction "IO23_37") (pintype "bidirectional"))
    )
    (net (code "142") (name "unconnected-(U3-IO25-Pad10)") (class "Default")
      (node (ref "U3") (pin "10") (pinfunction "IO25_10") (pintype "bidirectional"))
    )
    (net (code "143") (name "unconnected-(U3-IO26-Pad11)") (class "Default")
      (node (ref "U3") (pin "11") (pinfunction "IO26_11") (pintype "bidirectional"))
    )
    (net (code "144") (name "unconnected-(U3-IO27-Pad12)") (class "Default")
      (node (ref "U3") (pin "12") (pinfunction "IO27_12") (pintype "bidirectional"))
    )
    (net (code "145") (name "unconnected-(U3-IO32-Pad8)") (class "Default")
      (node (ref "U3") (pin "8") (pinfunction "IO32_8") (pintype "bidirectional"))
    )
    (net (code "146") (name "unconnected-(U3-IO33-Pad9)") (class "Default")
      (node (ref "U3") (pin "9") (pinfunction "IO33_9") (pintype "bidirectional"))
    )
    (net (code "147") (name "unconnected-(U3-IO34-Pad6)") (class "Default")
      (node (ref "U3") (pin "6") (pinfunction "IO34_6") (pintype "input"))
    )
    (net (code "148") (name "unconnected-(U3-IO35-Pad7)") (class "Default")
      (node (ref "U3") (pin "7") (pinfunction "IO35_7") (pintype "input"))
    )
    (net (code "149") (name "unconnected-(U3-SCK{slash}CLK-Pad20)") (class "Default")
      (node (ref "U3") (pin "20") (pinfunction "SCK/CLK_20") (pintype "bidirectional"))
    )
    (net (code "150") (name "unconnected-(U3-SCS{slash}CMD-Pad19)") (class "Default")
      (node (ref "U3") (pin "19") (pinfunction "SCS/CMD_19") (pintype "bidirectional"))
    )
    (net (code "151") (name "unconnected-(U3-SDI{slash}SD1-Pad22)") (class "Default")
      (node (ref "U3") (pin "22") (pinfunction "SDI/SD1_22") (pintype "bidirectional"))
    )
    (net (code "152") (name "unconnected-(U3-SDO{slash}SD0-Pad21)") (class "Default")
      (node (ref "U3") (pin "21") (pinfunction "SDO/SD0_21") (pintype "bidirectional"))
    )
    (net (code "153") (name "unconnected-(U3-SENSOR_VN-Pad5)") (class "Default")
      (node (ref "U3") (pin "5") (pinfunction "SENSOR_VN_5") (pintype "input"))
    )
    (net (code "154") (name "unconnected-(U3-SENSOR_VP-Pad4)") (class "Default")
      (node (ref "U3") (pin "4") (pinfunction "SENSOR_VP_4") (pintype "input"))
    )
    (net (code "155") (name "unconnected-(U3-SHD{slash}SD2-Pad17)") (class "Default")
      (node (ref "U3") (pin "17") (pinfunction "SHD/SD2_17") (pintype "bidirectional"))
    )
    (net (code "156") (name "unconnected-(U3-SWP{slash}SD3-Pad18)") (class "Default")
      (node (ref "U3") (pin "18") (pinfunction "SWP/SD3_18") (pintype "bidirectional"))
    )
  )
)
